# MicroRC-C.net
KiCad netlist of a schematic drawn in EAGLE
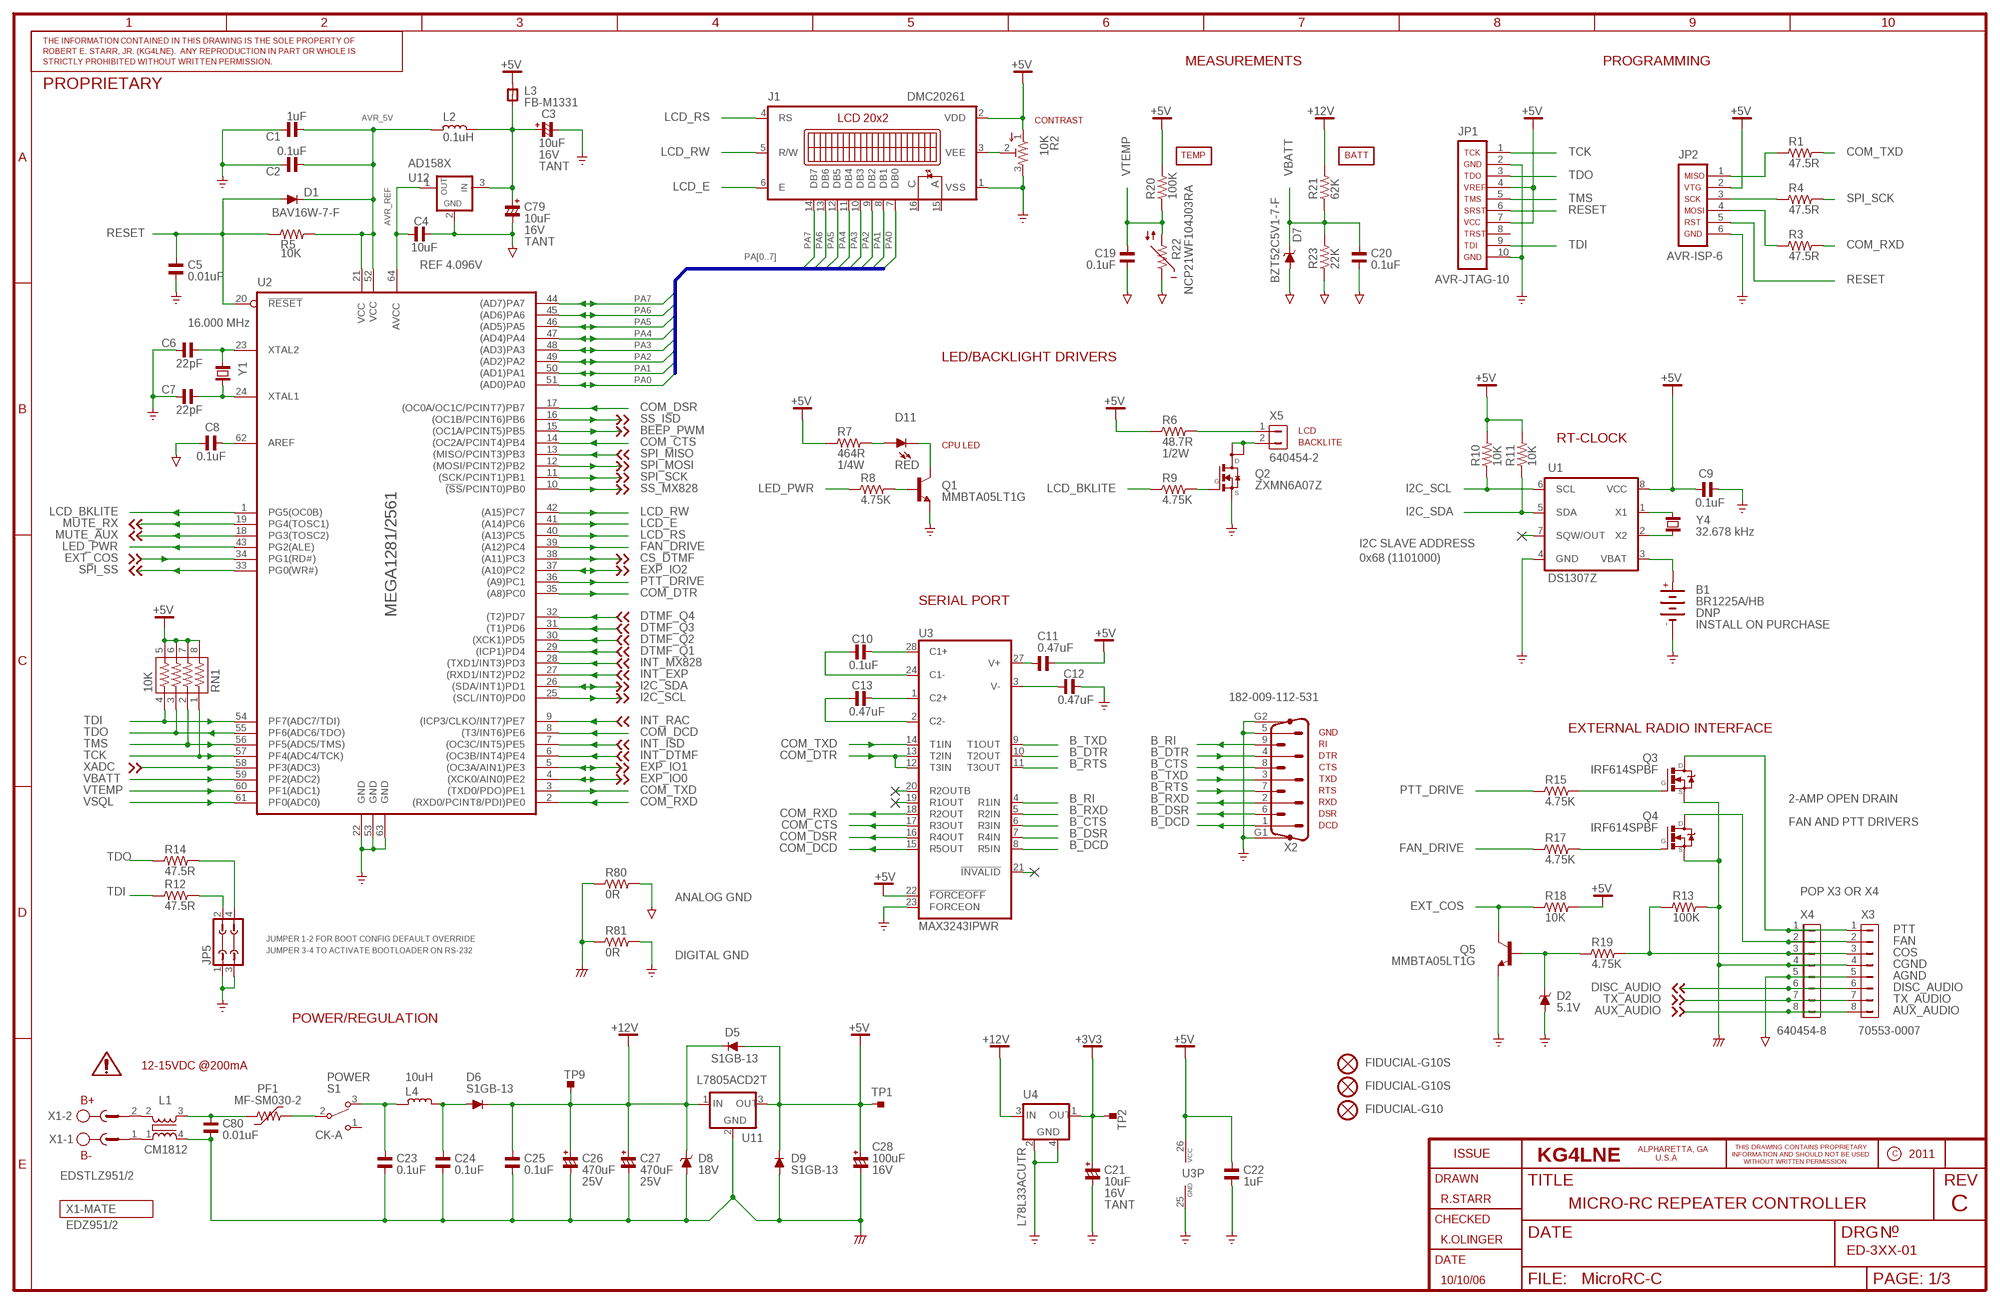
[diagram p0: schematic, sheet 1]
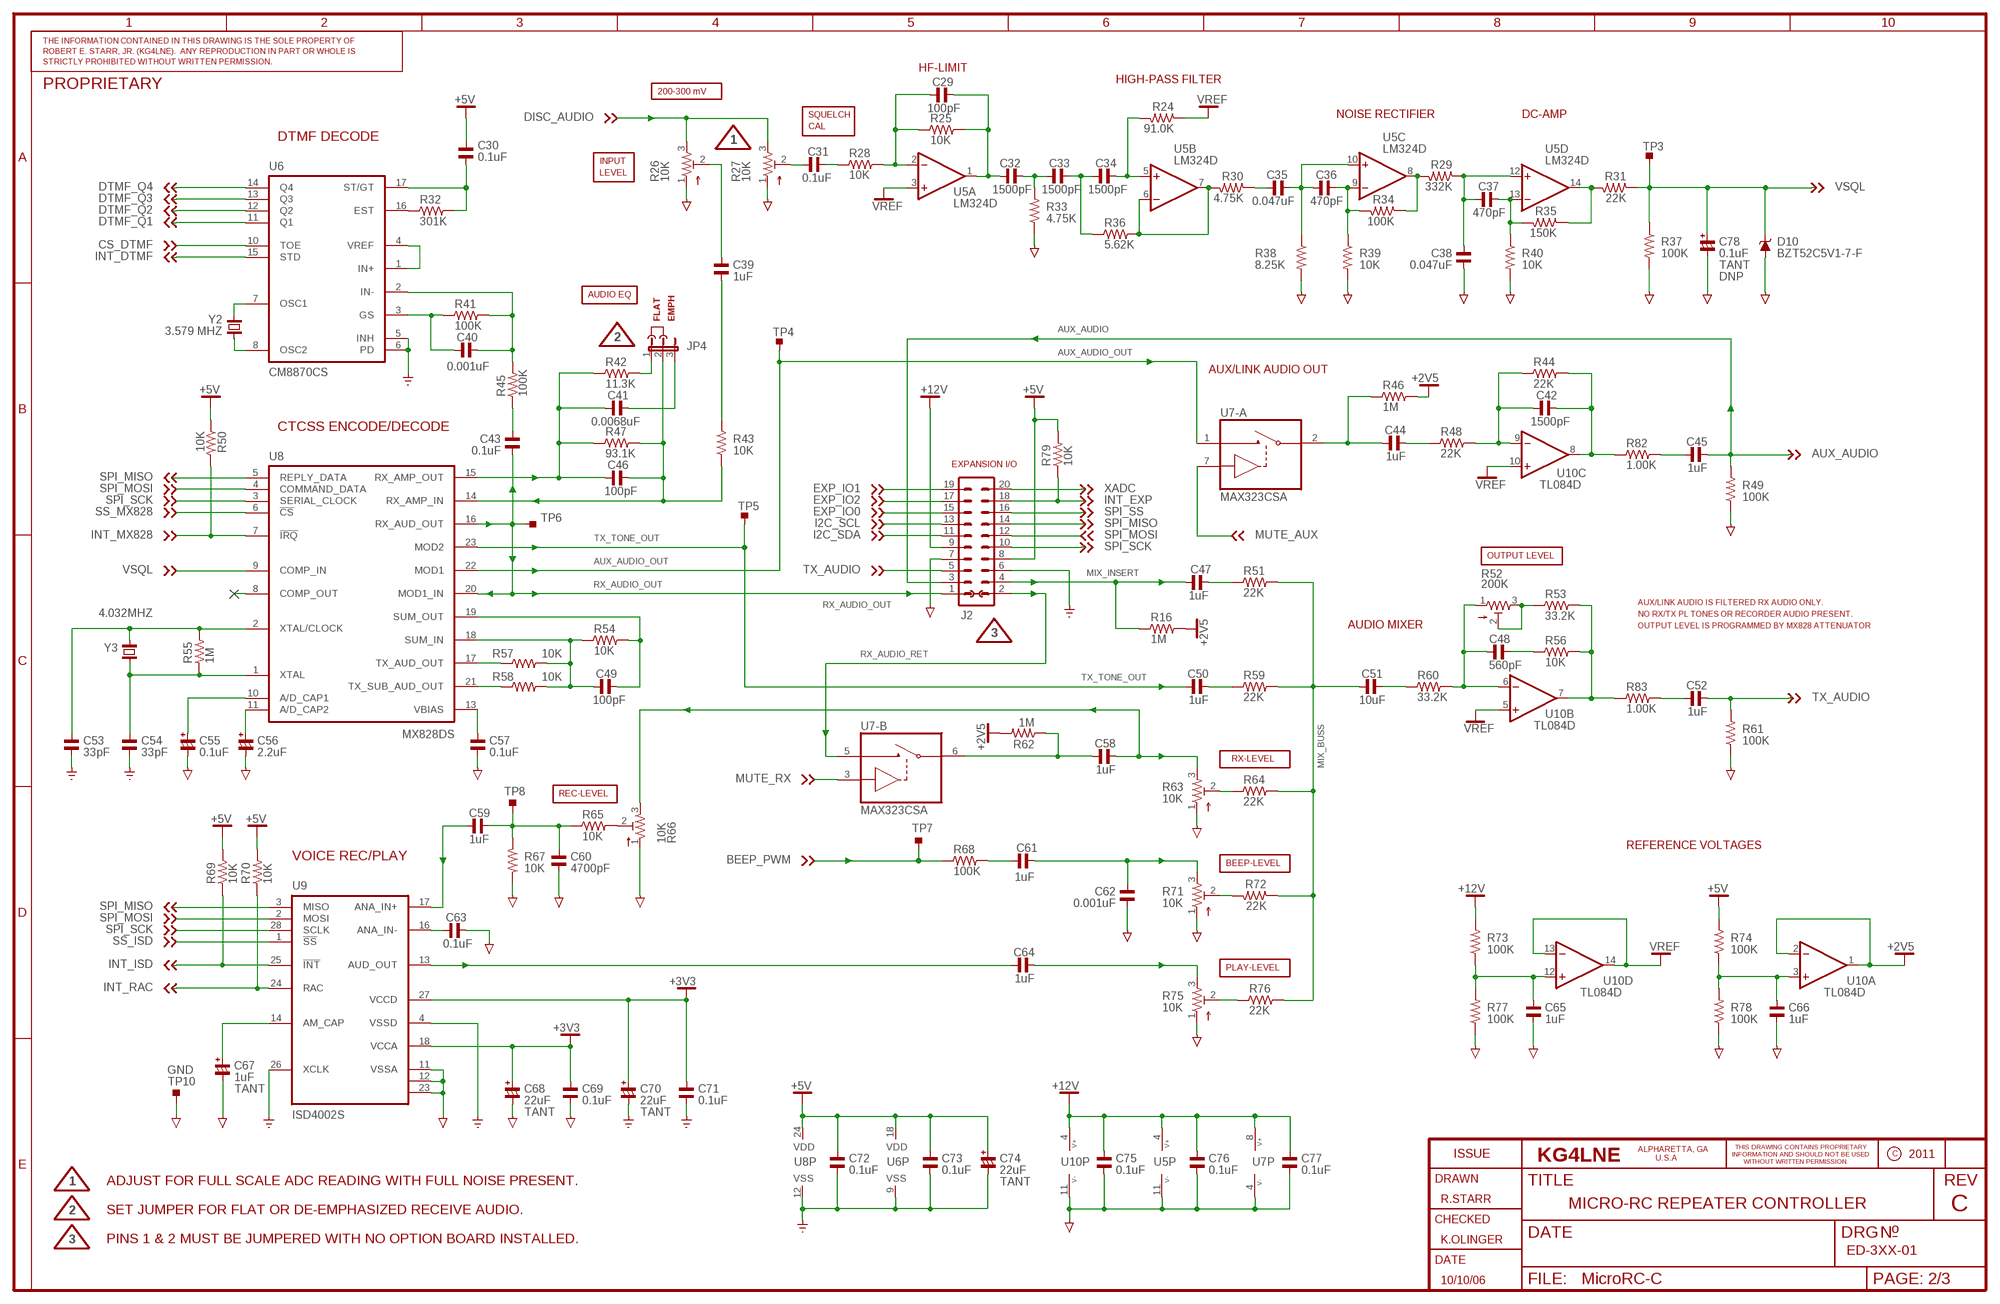
[diagram p1: schematic, sheet 2]
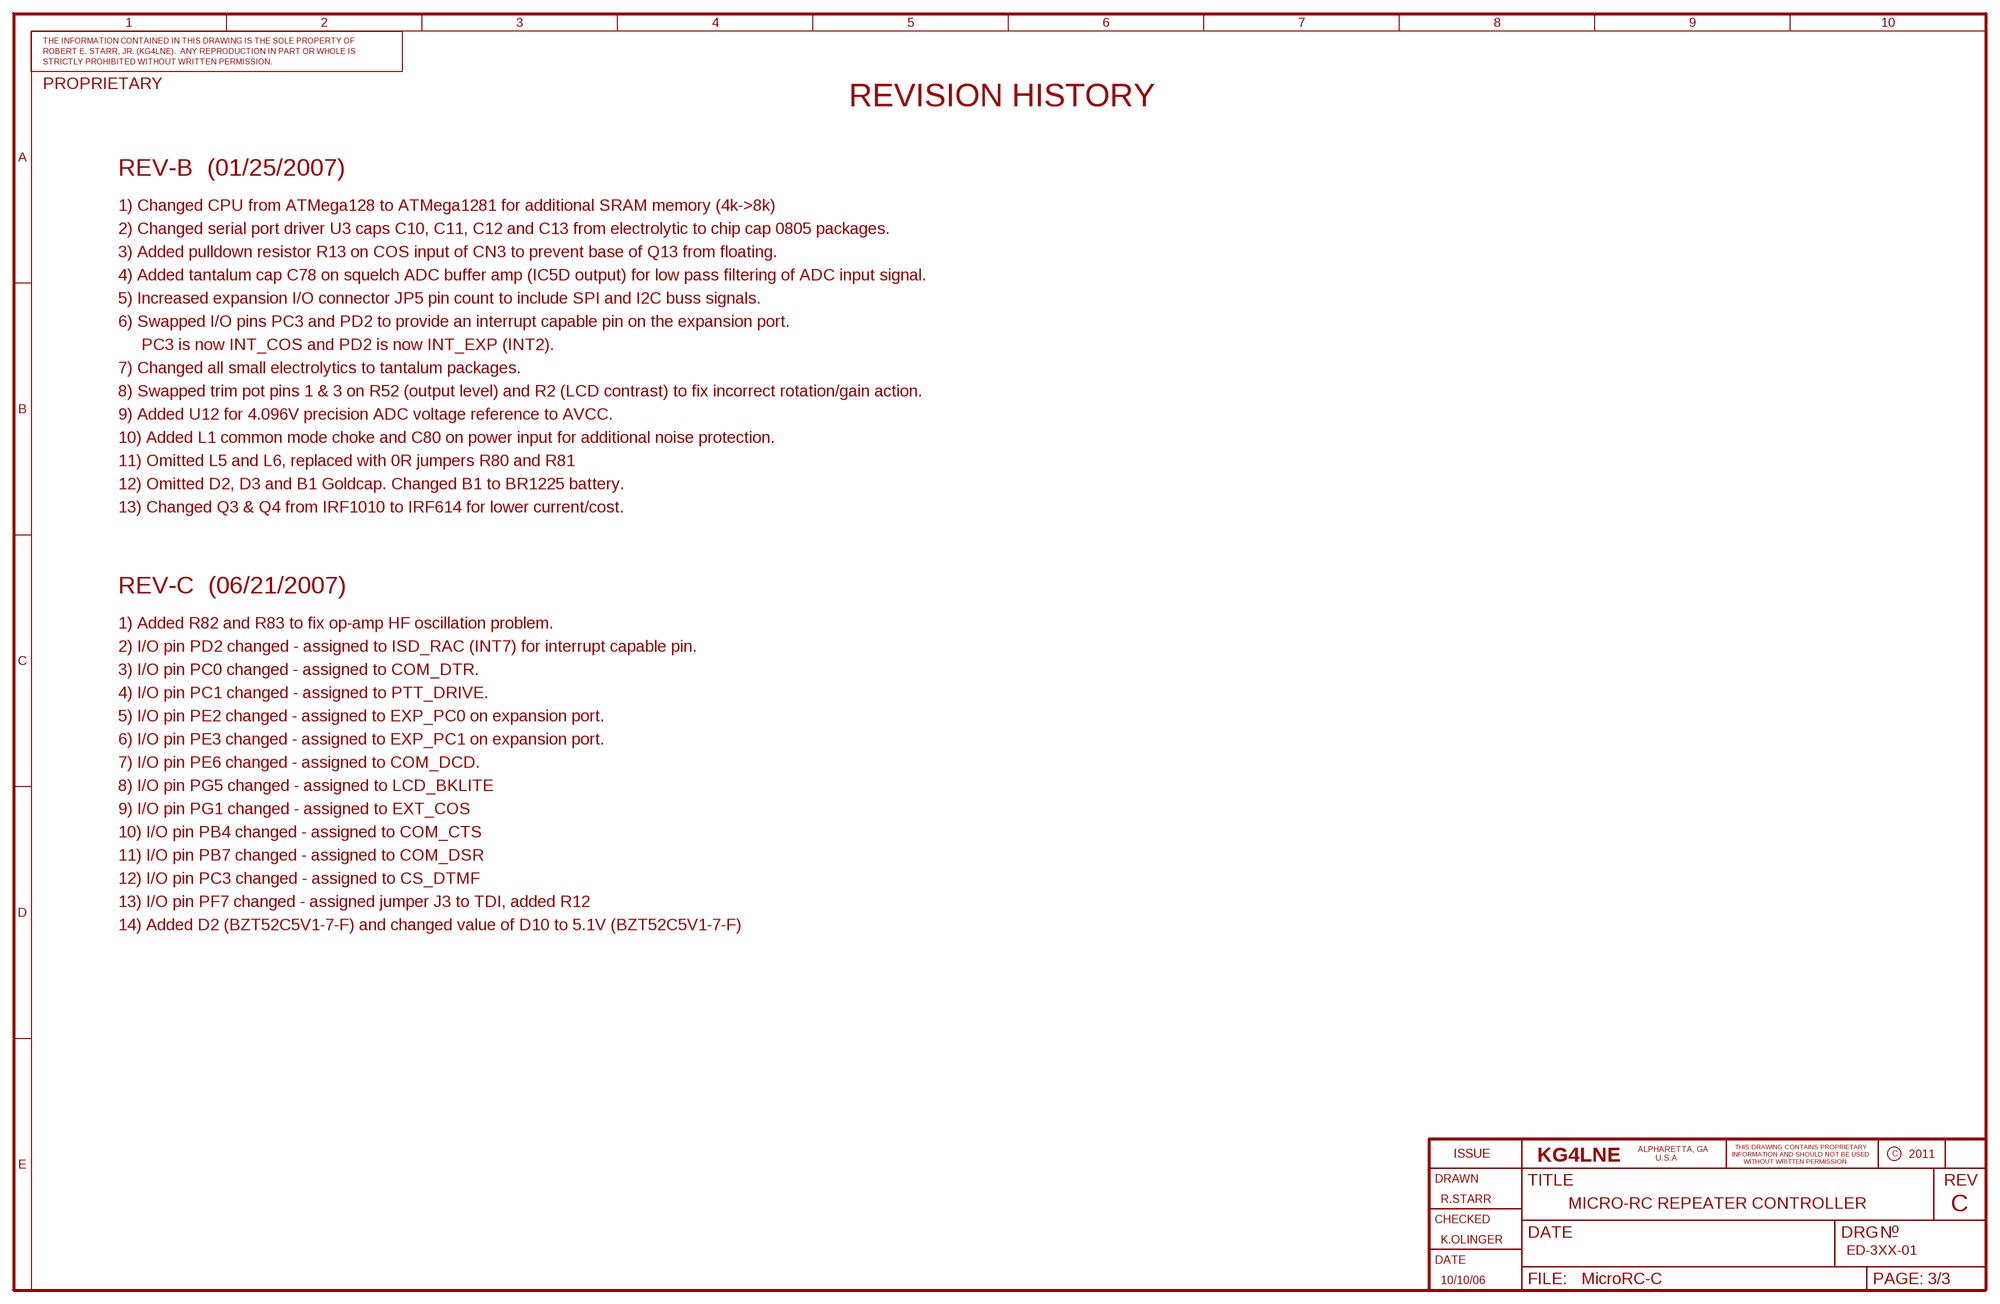
[diagram p2: schematic, sheet 3]

(export (version "E")
  (design (tool "Eeschema 10.0.6"))
  (components
    (comp (ref "B1")
      (value "BR1225A/HB")
      (footprint "eagle-import:BR1225")
      (fields (field (name "PLACE") "INSTALL ON PURCHASE"))
      (libsource (lib "eagle-import") (part "BR1225"))
    )
    (comp (ref "C1")
      (value "1uF")
      (footprint "eagle-import:C0805")
      (fields (field (name "PARTNO") "C0805C105Z3VACTU"))
      (libsource (lib "eagle-import") (part "C_0805"))
    )
    (comp (ref "C2")
      (value "0.1uF")
      (footprint "eagle-import:C0805")
      (fields (field (name "PARTNO") "C0805F104K5RACTU"))
      (libsource (lib "eagle-import") (part "C_0805"))
    )
    (comp (ref "C3")
      (value "10uF")
      (footprint "eagle-import:C3528_T")
      (fields
        (field (name "PARTNO") "T491B106M016AT")
        (field (name "TYPE") "TANT")
        (field (name "VOLT") "16V")
      )
      (libsource (lib "eagle-import") (part "CP_3528"))
    )
    (comp (ref "C4")
      (value "10uF")
      (footprint "eagle-import:C0805")
      (fields (field (name "PARTNO") "C0805C106K9PACTU"))
      (libsource (lib "eagle-import") (part "C_0805"))
    )
    (comp (ref "C5")
      (value "0.01uF")
      (footprint "eagle-import:C0805")
      (fields (field (name "PARTNO") "C0805C103K5RACTU"))
      (libsource (lib "eagle-import") (part "C_0805"))
    )
    (comp (ref "C6")
      (value "22pF")
      (footprint "eagle-import:C0805")
      (fields (field (name "PARTNO") "C0805C220J5GACTU"))
      (libsource (lib "eagle-import") (part "C_0805"))
    )
    (comp (ref "C7")
      (value "22pF")
      (footprint "eagle-import:C0805")
      (fields (field (name "PARTNO") "C0805C220J5GACTU"))
      (libsource (lib "eagle-import") (part "C_0805"))
    )
    (comp (ref "C8")
      (value "0.1uF")
      (footprint "eagle-import:C0805")
      (fields (field (name "PARTNO") "C0805F104K5RACTU"))
      (libsource (lib "eagle-import") (part "C_0805"))
    )
    (comp (ref "C9")
      (value "0.1uF")
      (footprint "eagle-import:C0805")
      (fields (field (name "PARTNO") "C0805F104K5RACTU"))
      (libsource (lib "eagle-import") (part "C_0805"))
    )
    (comp (ref "C10")
      (value "0.1uF")
      (footprint "eagle-import:C0805")
      (fields (field (name "PARTNO") "C0805F104K5RACTU"))
      (libsource (lib "eagle-import") (part "C_0805"))
    )
    (comp (ref "C11")
      (value "0.47uF")
      (footprint "eagle-import:C0805")
      (fields (field (name "PARTNO") "C0805F474K3RACTU"))
      (libsource (lib "eagle-import") (part "C_0805"))
    )
    (comp (ref "C12")
      (value "0.47uF")
      (footprint "eagle-import:C0805")
      (fields (field (name "PARTNO") "C0805F474K3RACTU"))
      (libsource (lib "eagle-import") (part "C_0805"))
    )
    (comp (ref "C13")
      (value "0.47uF")
      (footprint "eagle-import:C0805")
      (fields (field (name "PARTNO") "C0805F474K3RACTU"))
      (libsource (lib "eagle-import") (part "C_0805"))
    )
    (comp (ref "C19")
      (value "0.1uF")
      (footprint "eagle-import:C0805")
      (fields (field (name "PARTNO") "C0805F104K5RACTU"))
      (libsource (lib "eagle-import") (part "C_0805"))
    )
    (comp (ref "C20")
      (value "0.1uF")
      (footprint "eagle-import:C0805")
      (fields (field (name "PARTNO") "C0805F104K5RACTU"))
      (libsource (lib "eagle-import") (part "C_0805"))
    )
    (comp (ref "C21")
      (value "10uF")
      (footprint "eagle-import:C3528_T")
      (fields
        (field (name "PARTNO") "T491B106M016AT")
        (field (name "TYPE") "TANT")
        (field (name "VOLT") "16V")
      )
      (libsource (lib "eagle-import") (part "CP_3528"))
    )
    (comp (ref "C22")
      (value "1uF")
      (footprint "eagle-import:C0805")
      (fields (field (name "PARTNO") "C0805C105Z3VACTU"))
      (libsource (lib "eagle-import") (part "C_0805"))
    )
    (comp (ref "C23")
      (value "0.1uF")
      (footprint "eagle-import:C1206")
      (fields (field (name "PARTNO") "C1206C104K5RACTU"))
      (libsource (lib "eagle-import") (part "C_1206"))
    )
    (comp (ref "C24")
      (value "0.1uF")
      (footprint "eagle-import:C1206")
      (fields (field (name "PARTNO") "C1206C104K5RACTU"))
      (libsource (lib "eagle-import") (part "C_1206"))
    )
    (comp (ref "C25")
      (value "0.1uF")
      (footprint "eagle-import:C1206")
      (fields (field (name "PARTNO") "C1206C104K5RACTU"))
      (libsource (lib "eagle-import") (part "C_1206"))
    )
    (comp (ref "C26")
      (value "470uF")
      (footprint "eagle-import:CSV-G")
      (fields (field (name "PARTNO") "EEE-1EA471P") (field (name "VOLT") "25V"))
      (libsource (lib "eagle-import") (part "CP_SV-G"))
    )
    (comp (ref "C27")
      (value "470uF")
      (footprint "eagle-import:CSV-G")
      (fields (field (name "PARTNO") "EEE-1EA471P") (field (name "VOLT") "25V"))
      (libsource (lib "eagle-import") (part "CP_SV-G"))
    )
    (comp (ref "C28")
      (value "100uF")
      (footprint "eagle-import:CSV-E_F")
      (fields (field (name "PARTNO") "EEE-1CA101P") (field (name "VOLT") "16V"))
      (libsource (lib "eagle-import") (part "CP_SV-E/F"))
    )
    (comp (ref "C79")
      (value "10uF")
      (footprint "eagle-import:C3528_T")
      (fields
        (field (name "PARTNO") "T491B106M016AT")
        (field (name "TYPE") "TANT")
        (field (name "VOLT") "16V")
      )
      (libsource (lib "eagle-import") (part "CP_3528"))
    )
    (comp (ref "C80")
      (value "0.01uF")
      (footprint "eagle-import:C1206")
      (fields (field (name "PARTNO") "12065C103KAT2A"))
      (libsource (lib "eagle-import") (part "C_1206"))
    )
    (comp (ref "D1")
      (value "BAV16W-7-F")
      (footprint "eagle-import:SOD123")
      (libsource (lib "eagle-import") (part "DIODE-SOD123"))
    )
    (comp (ref "D2")
      (value "5.1V")
      (footprint "eagle-import:SOD123")
      (fields (field (name "PARTNO") "BZT52C5V1-7-F"))
      (libsource (lib "eagle-import") (part "ZENER-DIODESOD123"))
    )
    (comp (ref "D5")
      (value "S1GB-13")
      (footprint "eagle-import:SMB")
      (fields (field (name "PARTNO") "RS1GB-13-F"))
      (libsource (lib "eagle-import") (part "S1GB-13"))
    )
    (comp (ref "D6")
      (value "S1GB-13")
      (footprint "eagle-import:SMB")
      (fields (field (name "PARTNO") "RS1GB-13-F"))
      (libsource (lib "eagle-import") (part "S1GB-13"))
    )
    (comp (ref "D7")
      (value "BZT52C5V1-7-F")
      (footprint "eagle-import:SOD123")
      (fields (field (name "PARTNO") "BZT52C5V6-7-F"))
      (libsource (lib "eagle-import") (part "ZENER-DIODESOD123"))
    )
    (comp (ref "D8")
      (value "18V")
      (footprint "eagle-import:SMB")
      (fields (field (name "PARTNO") "1SMB5931BT3G"))
      (libsource (lib "eagle-import") (part "ZENER-DIODESMB"))
    )
    (comp (ref "D9")
      (value "S1GB-13")
      (footprint "eagle-import:SMB")
      (fields (field (name "PARTNO") "RS1GB-13-F"))
      (libsource (lib "eagle-import") (part "S1GB-13"))
    )
    (comp (ref "D11")
      (value "RED")
      (footprint "eagle-import:LED535")
      (fields (field (name "PARTNO") "5350T5"))
      (libsource (lib "eagle-import") (part "LED535XX"))
    )
    (comp (ref "FIDUCIAL1")
      (value "FIDUCIAL-G10S")
      (footprint "eagle-import:G10S")
      (libsource (lib "eagle-import") (part "FIDUCIAL-G10S"))
    )
    (comp (ref "FIDUCIAL2")
      (value "FIDUCIAL-G10S")
      (footprint "eagle-import:G10S")
      (libsource (lib "eagle-import") (part "FIDUCIAL-G10S"))
    )
    (comp (ref "FIDUCIAL3")
      (value "FIDUCIAL-G10")
      (footprint "eagle-import:G10")
      (libsource (lib "eagle-import") (part "FIDUCIAL-G10"))
    )
    (comp (ref "J1")
      (value "DMC20261")
      (footprint "eagle-import:DMC20261")
      (libsource (lib "eagle-import") (part "DMC20261"))
    )
    (comp (ref "JP1")
      (value "AVR-JTAG-10")
      (footprint "eagle-import:AVR-JTAG-10")
      (libsource (lib "eagle-import") (part "AVR-JTAG-10"))
    )
    (comp (ref "JP2")
      (value "AVR-ISP-6")
      (footprint "eagle-import:AVR-ISP-6")
      (libsource (lib "eagle-import") (part "AVR-ISP-6"))
    )
    (comp (ref "JP5")
      (value "JP2Q")
      (footprint "eagle-import:JP2Q")
      (libsource (lib "eagle-import") (part "JP2Q"))
    )
    (comp (ref "L1")
      (value "CM1812")
      (footprint "eagle-import:CM1812")
      (fields (field (name "PARTNO") "CM1812R600R-10"))
      (libsource (lib "eagle-import") (part "CM1812"))
    )
    (comp (ref "L2")
      (value "0.1uH")
      (footprint "eagle-import:L1206")
      (fields (field (name "PARTNO") "PM1210-R10J"))
      (libsource (lib "eagle-import") (part "L_1206"))
    )
    (comp (ref "L3")
      (value "FB-M1331")
      (footprint "eagle-import:L1206")
      (fields (field (name "PARTNO") "PM2001-200"))
      (libsource (lib "eagle-import") (part "FB_1206"))
    )
    (comp (ref "L4")
      (value "10uH")
      (footprint "eagle-import:PM-13")
      (fields (field (name "PARTNO") "PM3308-100M"))
      (libsource (lib "eagle-import") (part "L-PM3308"))
    )
    (comp (ref "PF1")
      (value "MF-SM030-2")
      (footprint "eagle-import:SMD-7555")
      (libsource (lib "eagle-import") (part "POLYSWITCH-SMD-7555"))
    )
    (comp (ref "Q1")
      (value "MMBTA05LT1G")
      (footprint "eagle-import:SOT23")
      (libsource (lib "eagle-import") (part "MMBTA05"))
    )
    (comp (ref "Q2")
      (value "ZXMN6A07Z")
      (footprint "eagle-import:SOT89")
      (fields (field (name "PARTNO") "ZXMN6A07ZTA"))
      (libsource (lib "eagle-import") (part "ZXMN6A07Z"))
    )
    (comp (ref "Q3")
      (value "IRF614SPBF")
      (footprint "eagle-import:D2PAK")
      (libsource (lib "eagle-import") (part "IRF614"))
    )
    (comp (ref "Q4")
      (value "IRF614SPBF")
      (footprint "eagle-import:D2PAK")
      (libsource (lib "eagle-import") (part "IRF614"))
    )
    (comp (ref "Q5")
      (value "MMBTA05LT1G")
      (footprint "eagle-import:SOT23")
      (libsource (lib "eagle-import") (part "MMBTA05"))
    )
    (comp (ref "R1")
      (value "47.5R")
      (footprint "eagle-import:R0805")
      (fields (field (name "PARTNO") "ERJ-6ENF47R5V"))
      (libsource (lib "eagle-import") (part "R_0805"))
    )
    (comp (ref "R2")
      (value "10K")
      (footprint "eagle-import:EVM-L4G")
      (fields (field (name "PARTNO") "EVM-L4GA00B14"))
      (libsource (lib "eagle-import") (part "TRIM_EU-EVM-L4G"))
    )
    (comp (ref "R3")
      (value "47.5R")
      (footprint "eagle-import:R0805")
      (fields (field (name "PARTNO") "ERJ-6ENF47R5V"))
      (libsource (lib "eagle-import") (part "R_0805"))
    )
    (comp (ref "R4")
      (value "47.5R")
      (footprint "eagle-import:R0805")
      (fields (field (name "PARTNO") "ERJ-6ENF47R5V"))
      (libsource (lib "eagle-import") (part "R_0805"))
    )
    (comp (ref "R5")
      (value "10K")
      (footprint "eagle-import:R0805")
      (fields (field (name "PARTNO") "ERJ-6ENF1002V"))
      (libsource (lib "eagle-import") (part "R_0805"))
    )
    (comp (ref "R6")
      (value "48.7R")
      (footprint "eagle-import:R2010")
      (fields (field (name "PARTNO") "ERJ-12SF48R7U") (field (name "RATE") "1/2W"))
      (libsource (lib "eagle-import") (part "R_2010"))
    )
    (comp (ref "R7")
      (value "464R")
      (footprint "eagle-import:R1210")
      (fields (field (name "PARTNO") "ERJ-14NF4640U") (field (name "RATE") "1/4W"))
      (libsource (lib "eagle-import") (part "R_1210"))
    )
    (comp (ref "R8")
      (value "4.75K")
      (footprint "eagle-import:R0805")
      (fields (field (name "PARTNO") "ERJ-6ENF4751V"))
      (libsource (lib "eagle-import") (part "R_0805"))
    )
    (comp (ref "R9")
      (value "4.75K")
      (footprint "eagle-import:R0805")
      (fields (field (name "PARTNO") "ERJ-6ENF4751V"))
      (libsource (lib "eagle-import") (part "R_0805"))
    )
    (comp (ref "R10")
      (value "10K")
      (footprint "eagle-import:R0805")
      (fields (field (name "PARTNO") "ERJ-6ENF1002V"))
      (libsource (lib "eagle-import") (part "R_0805"))
    )
    (comp (ref "R11")
      (value "10K")
      (footprint "eagle-import:R0805")
      (fields (field (name "PARTNO") "ERJ-6ENF1002V"))
      (libsource (lib "eagle-import") (part "R_0805"))
    )
    (comp (ref "R12")
      (value "47.5R")
      (footprint "eagle-import:R0805")
      (fields (field (name "PARTNO") "ERJ-6ENF47R5V"))
      (libsource (lib "eagle-import") (part "R_0805"))
    )
    (comp (ref "R13")
      (value "100K")
      (footprint "eagle-import:R0805")
      (fields (field (name "PARTNO") "ERJ-6ENF1003V"))
      (libsource (lib "eagle-import") (part "R_0805"))
    )
    (comp (ref "R14")
      (value "47.5R")
      (footprint "eagle-import:R0805")
      (fields (field (name "PARTNO") "ERJ-6ENF47R5V"))
      (libsource (lib "eagle-import") (part "R_0805"))
    )
    (comp (ref "R15")
      (value "4.75K")
      (footprint "eagle-import:R0805")
      (fields (field (name "PARTNO") "ERJ-6ENF4751V"))
      (libsource (lib "eagle-import") (part "R_0805"))
    )
    (comp (ref "R17")
      (value "4.75K")
      (footprint "eagle-import:R0805")
      (fields (field (name "PARTNO") "ERJ-6ENF4751V"))
      (libsource (lib "eagle-import") (part "R_0805"))
    )
    (comp (ref "R18")
      (value "10K")
      (footprint "eagle-import:R0805")
      (fields (field (name "PARTNO") "ERJ-6ENF1002V"))
      (libsource (lib "eagle-import") (part "R_0805"))
    )
    (comp (ref "R19")
      (value "4.75K")
      (footprint "eagle-import:R0805")
      (fields (field (name "PARTNO") "ERJ-6ENF4751V"))
      (libsource (lib "eagle-import") (part "R_0805"))
    )
    (comp (ref "R20")
      (value "100K")
      (footprint "eagle-import:R0805")
      (fields (field (name "PARTNO") "ERJ-6ENF1003V"))
      (libsource (lib "eagle-import") (part "R_0805"))
    )
    (comp (ref "R21")
      (value "62K")
      (footprint "eagle-import:R0805")
      (fields (field (name "PARTNO") "ERJ-6ENF6192V"))
      (libsource (lib "eagle-import") (part "R_0805"))
    )
    (comp (ref "R22")
      (value "NCP21WF104J03RA")
      (footprint "eagle-import:R0805")
      (libsource (lib "eagle-import") (part "NCP-0805"))
    )
    (comp (ref "R23")
      (value "22K")
      (footprint "eagle-import:R0805")
      (fields (field (name "PARTNO") "ERJ-6ENF2212V"))
      (libsource (lib "eagle-import") (part "R_0805"))
    )
    (comp (ref "R80")
      (value "0R")
      (footprint "eagle-import:R0805")
      (fields (field (name "PARTNO") "RC0805JR-070RL"))
      (libsource (lib "eagle-import") (part "R_0805"))
    )
    (comp (ref "R81")
      (value "0R")
      (footprint "eagle-import:R0805")
      (fields (field (name "PARTNO") "RC0805JR-070RL"))
      (libsource (lib "eagle-import") (part "R_0805"))
    )
    (comp (ref "RN1")
      (value "10K")
      (footprint "eagle-import:744-8")
      (fields (field (name "PARTNO") "744C083103JPTR"))
      (libsource (lib "eagle-import") (part "744-8"))
    )
    (comp (ref "S1")
      (value "CK-A")
      (footprint "eagle-import:CK-A")
      (fields (field (name "PARTNO") "2M1-SP1-T2-B4-M6RE"))
      (libsource (lib "eagle-import") (part "CK-A"))
    )
    (comp (ref "TP1")
      (value "TPTP10SQ")
      (footprint "eagle-import:TP10SQ")
      (libsource (lib "eagle-import") (part "TPTP10SQ"))
    )
    (comp (ref "TP2")
      (value "TPTP10SQ")
      (footprint "eagle-import:TP10SQ")
      (libsource (lib "eagle-import") (part "TPTP10SQ"))
    )
    (comp (ref "TP9")
      (value "TPTP10SQ")
      (footprint "eagle-import:TP10SQ")
      (libsource (lib "eagle-import") (part "TPTP10SQ"))
    )
    (comp (ref "U1")
      (value "DS1307Z")
      (footprint "eagle-import:SO08")
      (fields (field (name "PARTNO") "DS1307Z+"))
      (libsource (lib "eagle-import") (part "DS1307Z"))
    )
    (comp (ref "U2")
      (value "MEGA1281/2561")
      (footprint "eagle-import:TQFP64-AEB")
      (fields (field (name "PARTNO") "ATMEGA1281-16AU"))
      (libsource (lib "eagle-import") (part "MEGA1281/2561"))
    )
    (comp (ref "U3")
      (value "MAX3243IPWR")
      (footprint "eagle-import:TSSOP28")
      (fields (field (name "PARTNO") "MAX3243ECPWR"))
      (libsource (lib "eagle-import") (part "MAX3243PW"))
    )
    (comp (ref "U4")
      (value "L78L33ACUTR")
      (footprint "eagle-import:SOT89-4")
      (libsource (lib "eagle-import") (part "L78LXXCU/BU"))
    )
    (comp (ref "U11")
      (value "L7805ACD2T")
      (footprint "eagle-import:D2PAK")
      (libsource (lib "eagle-import") (part "L78XXD2T"))
    )
    (comp (ref "U12")
      (value "AD158X")
      (footprint "eagle-import:SOT23")
      (fields (field (name "PARTNO") "AD1584BRTZ-REEL7"))
      (libsource (lib "eagle-import") (part "AD158X"))
    )
    (comp (ref "X1")
      (value "EDSTLZ951/2")
      (footprint "eagle-import:951-2")
      (fields (field (name "PARTNO") "EDSTLZ951/2"))
      (libsource (lib "eagle-import") (part "EDSTLZ-2-951"))
    )
    (comp (ref "X2")
      (value "182-009-112-531")
      (footprint "eagle-import:NC182M9")
      (fields (field (name "PARTNO") "182-009-113R531"))
      (libsource (lib "eagle-import") (part "NC182M9-VS"))
    )
    (comp (ref "X3")
      (value "70553-0007")
      (footprint "eagle-import:70553-08")
      (fields (field (name "PLACE") "POP X3 OR X4"))
      (libsource (lib "eagle-import") (part "HDR-1X8-70553-?"))
    )
    (comp (ref "X4")
      (value "640454-8")
      (footprint "eagle-import:MTA08-100")
      (libsource (lib "eagle-import") (part "MTA08-100"))
    )
    (comp (ref "X5")
      (value "640454-2")
      (footprint "eagle-import:MTA-100-2V")
      (libsource (lib "eagle-import") (part "HDR-1X2-MTA-100"))
    )
    (comp (ref "Y1")
      (value "16.000 MHz")
      (footprint "eagle-import:TC38H")
      (fields (field (name "PARTNO") "ECS-160-18-9X"))
      (libsource (lib "eagle-import") (part "CRYTALTC38H"))
    )
    (comp (ref "Y4")
      (value "32.678 kHz")
      (footprint "eagle-import:TC26H")
      (fields (field (name "PARTNO") "ECS-.327-12.5-13X"))
      (libsource (lib "eagle-import") (part "CRYTALTC26H"))
    )
    (comp (ref "C29")
      (value "100pF")
      (footprint "eagle-import:C0805")
      (fields (field (name "PARTNO") "C0805C101J5GACTU"))
      (libsource (lib "eagle-import") (part "C_0805"))
    )
    (comp (ref "C30")
      (value "0.1uF")
      (footprint "eagle-import:C0805")
      (fields (field (name "PARTNO") "C0805F104K5RACTU"))
      (libsource (lib "eagle-import") (part "C_0805"))
    )
    (comp (ref "C31")
      (value "0.1uF")
      (footprint "eagle-import:C0805")
      (fields (field (name "PARTNO") "C0805F104K5RACTU"))
      (libsource (lib "eagle-import") (part "C_0805"))
    )
    (comp (ref "C32")
      (value "1500pF")
      (footprint "eagle-import:C0805")
      (fields (field (name "PARTNO") "C0805C152K5RACTU"))
      (libsource (lib "eagle-import") (part "C_0805"))
    )
    (comp (ref "C33")
      (value "1500pF")
      (footprint "eagle-import:C0805")
      (fields (field (name "PARTNO") "C0805C152K5RACTU"))
      (libsource (lib "eagle-import") (part "C_0805"))
    )
    (comp (ref "C34")
      (value "1500pF")
      (footprint "eagle-import:C0805")
      (fields (field (name "PARTNO") "C0805C152K5RACTU"))
      (libsource (lib "eagle-import") (part "C_0805"))
    )
    (comp (ref "C35")
      (value "0.047uF")
      (footprint "eagle-import:C0805")
      (fields (field (name "PARTNO") "C0805C473K5RACTU"))
      (libsource (lib "eagle-import") (part "C_0805"))
    )
    (comp (ref "C36")
      (value "470pF")
      (footprint "eagle-import:C0805")
      (fields (field (name "PARTNO") "C0805C471J5GACTU"))
      (libsource (lib "eagle-import") (part "C_0805"))
    )
    (comp (ref "C37")
      (value "470pF")
      (footprint "eagle-import:C0805")
      (fields (field (name "PARTNO") "C0805C471J5GACTU"))
      (libsource (lib "eagle-import") (part "C_0805"))
    )
    (comp (ref "C38")
      (value "0.047uF")
      (footprint "eagle-import:C0805")
      (fields (field (name "PARTNO") "C0805C473K5RACTU"))
      (libsource (lib "eagle-import") (part "C_0805"))
    )
    (comp (ref "C39")
      (value "1uF")
      (footprint "eagle-import:C0805")
      (fields (field (name "PARTNO") "C0805C105Z3VACTU"))
      (libsource (lib "eagle-import") (part "C_0805"))
    )
    (comp (ref "C40")
      (value "0.001uF")
      (footprint "eagle-import:C0805")
      (fields (field (name "PARTNO") "C0805C102K5RACTU"))
      (libsource (lib "eagle-import") (part "C_0805"))
    )
    (comp (ref "C41")
      (value "0.0068uF")
      (footprint "eagle-import:C0805")
      (fields (field (name "PARTNO") "C0805C682K5RACTU"))
      (libsource (lib "eagle-import") (part "C_0805"))
    )
    (comp (ref "C42")
      (value "1500pF")
      (footprint "eagle-import:C0805")
      (fields (field (name "PARTNO") "C0805C152K5RACTU"))
      (libsource (lib "eagle-import") (part "C_0805"))
    )
    (comp (ref "C43")
      (value "0.1uF")
      (footprint "eagle-import:C0805")
      (fields (field (name "PARTNO") "C0805F104K5RACTU"))
      (libsource (lib "eagle-import") (part "C_0805"))
    )
    (comp (ref "C44")
      (value "1uF")
      (footprint "eagle-import:C0805")
      (fields (field (name "PARTNO") "C0805C105Z3VACTU"))
      (libsource (lib "eagle-import") (part "C_0805"))
    )
    (comp (ref "C45")
      (value "1uF")
      (footprint "eagle-import:C0805")
      (fields (field (name "PARTNO") "C0805C105Z3VACTU"))
      (libsource (lib "eagle-import") (part "C_0805"))
    )
    (comp (ref "C46")
      (value "100pF")
      (footprint "eagle-import:C0805")
      (fields (field (name "PARTNO") "C0805C101J5GACTU"))
      (libsource (lib "eagle-import") (part "C_0805"))
    )
    (comp (ref "C47")
      (value "1uF")
      (footprint "eagle-import:C0805")
      (fields (field (name "PARTNO") "C0805C105Z3VACTU"))
      (libsource (lib "eagle-import") (part "C_0805"))
    )
    (comp (ref "C48")
      (value "560pF")
      (footprint "eagle-import:C0805")
      (fields (field (name "PARTNO") "C0805C561J5GACTU"))
      (libsource (lib "eagle-import") (part "C_0805"))
    )
    (comp (ref "C49")
      (value "100pF")
      (footprint "eagle-import:C0805")
      (fields (field (name "PARTNO") "C0805C101J5GACTU"))
      (libsource (lib "eagle-import") (part "C_0805"))
    )
    (comp (ref "C50")
      (value "1uF")
      (footprint "eagle-import:C0805")
      (fields (field (name "PARTNO") "C0805C105Z3VACTU"))
      (libsource (lib "eagle-import") (part "C_0805"))
    )
    (comp (ref "C51")
      (value "10uF")
      (footprint "eagle-import:C0805")
      (fields (field (name "PARTNO") "C0805C106K9PACTU"))
      (libsource (lib "eagle-import") (part "C_0805"))
    )
    (comp (ref "C52")
      (value "1uF")
      (footprint "eagle-import:C0805")
      (fields (field (name "PARTNO") "C0805C105Z3VACTU"))
      (libsource (lib "eagle-import") (part "C_0805"))
    )
    (comp (ref "C53")
      (value "33pF")
      (footprint "eagle-import:C0805")
      (fields (field (name "PARTNO") "C0805C330J5GACTU"))
      (libsource (lib "eagle-import") (part "C_0805"))
    )
    (comp (ref "C54")
      (value "33pF")
      (footprint "eagle-import:C0805")
      (fields (field (name "PARTNO") "C0805C330J5GACTU"))
      (libsource (lib "eagle-import") (part "C_0805"))
    )
    (comp (ref "C55")
      (value "0.1uF")
      (footprint "eagle-import:C3216_T")
      (fields (field (name "PARTNO") "T491A104K035AT"))
      (libsource (lib "eagle-import") (part "CP_3216"))
    )
    (comp (ref "C56")
      (value "2.2uF")
      (footprint "eagle-import:C3216_T")
      (fields (field (name "PARTNO") "T491A225K010AT"))
      (libsource (lib "eagle-import") (part "CP_3216"))
    )
    (comp (ref "C57")
      (value "0.1uF")
      (footprint "eagle-import:C0805")
      (fields (field (name "PARTNO") "C0805F104K5RACTU"))
      (libsource (lib "eagle-import") (part "C_0805"))
    )
    (comp (ref "C58")
      (value "1uF")
      (footprint "eagle-import:C0805")
      (fields (field (name "PARTNO") "C0805C105Z3VACTU"))
      (libsource (lib "eagle-import") (part "C_0805"))
    )
    (comp (ref "C59")
      (value "1uF")
      (footprint "eagle-import:C0805")
      (fields (field (name "PARTNO") "C0805C105Z3VACTU"))
      (libsource (lib "eagle-import") (part "C_0805"))
    )
    (comp (ref "C60")
      (value "4700pF")
      (footprint "eagle-import:C0805")
      (fields (field (name "PARTNO") "C0805C472K5RACTU"))
      (libsource (lib "eagle-import") (part "C_0805"))
    )
    (comp (ref "C61")
      (value "1uF")
      (footprint "eagle-import:C0805")
      (fields (field (name "PARTNO") "C0805C105Z3VACTU"))
      (libsource (lib "eagle-import") (part "C_0805"))
    )
    (comp (ref "C62")
      (value "0.001uF")
      (footprint "eagle-import:C0805")
      (fields (field (name "PARTNO") "C0805C102K5RACTU"))
      (libsource (lib "eagle-import") (part "C_0805"))
    )
    (comp (ref "C63")
      (value "0.1uF")
      (footprint "eagle-import:C0805")
      (fields (field (name "PARTNO") "C0805F104K5RACTU"))
      (libsource (lib "eagle-import") (part "C_0805"))
    )
    (comp (ref "C64")
      (value "1uF")
      (footprint "eagle-import:C0805")
      (fields (field (name "PARTNO") "C0805C105Z3VACTU"))
      (libsource (lib "eagle-import") (part "C_0805"))
    )
    (comp (ref "C65")
      (value "1uF")
      (footprint "eagle-import:C0805")
      (fields (field (name "PARTNO") "C0805C105Z3VACTU"))
      (libsource (lib "eagle-import") (part "C_0805"))
    )
    (comp (ref "C66")
      (value "1uF")
      (footprint "eagle-import:C0805")
      (fields (field (name "PARTNO") "C0805C105Z3VACTU"))
      (libsource (lib "eagle-import") (part "C_0805"))
    )
    (comp (ref "C67")
      (value "1uF")
      (footprint "eagle-import:C3216_T")
      (fields (field (name "PARTNO") "T491A105K016AT") (field (name "TYPE") "TANT"))
      (libsource (lib "eagle-import") (part "CP_3216"))
    )
    (comp (ref "C68")
      (value "22uF")
      (footprint "eagle-import:C3528_T")
      (fields (field (name "PARTNO") "T491B226M016AT") (field (name "TYPE") "TANT"))
      (libsource (lib "eagle-import") (part "CP_3528"))
    )
    (comp (ref "C69")
      (value "0.1uF")
      (footprint "eagle-import:C0805")
      (fields (field (name "PARTNO") "C0805F104K5RACTU"))
      (libsource (lib "eagle-import") (part "C_0805"))
    )
    (comp (ref "C70")
      (value "22uF")
      (footprint "eagle-import:C3528_T")
      (fields (field (name "PARTNO") "T491B226M016AT") (field (name "TYPE") "TANT"))
      (libsource (lib "eagle-import") (part "CP_3528"))
    )
    (comp (ref "C71")
      (value "0.1uF")
      (footprint "eagle-import:C0805")
      (fields (field (name "PARTNO") "C0805F104K5RACTU"))
      (libsource (lib "eagle-import") (part "C_0805"))
    )
    (comp (ref "C72")
      (value "0.1uF")
      (footprint "eagle-import:C0805")
      (fields (field (name "PARTNO") "C0805F104K5RACTU"))
      (libsource (lib "eagle-import") (part "C_0805"))
    )
    (comp (ref "C73")
      (value "0.1uF")
      (footprint "eagle-import:C0805")
      (fields (field (name "PARTNO") "C0805F104K5RACTU"))
      (libsource (lib "eagle-import") (part "C_0805"))
    )
    (comp (ref "C74")
      (value "22uF")
      (footprint "eagle-import:C3528_T")
      (fields (field (name "PARTNO") "T491B226M016AT") (field (name "TYPE") "TANT"))
      (libsource (lib "eagle-import") (part "CP_3528"))
    )
    (comp (ref "C75")
      (value "0.1uF")
      (footprint "eagle-import:C0805")
      (fields (field (name "PARTNO") "C0805F104K5RACTU"))
      (libsource (lib "eagle-import") (part "C_0805"))
    )
    (comp (ref "C76")
      (value "0.1uF")
      (footprint "eagle-import:C0805")
      (fields (field (name "PARTNO") "C0805F104K5RACTU"))
      (libsource (lib "eagle-import") (part "C_0805"))
    )
    (comp (ref "C77")
      (value "0.1uF")
      (footprint "eagle-import:C0805")
      (fields (field (name "PARTNO") "C0805F104K5RACTU"))
      (libsource (lib "eagle-import") (part "C_0805"))
    )
    (comp (ref "C78")
      (value "0.1uF")
      (footprint "eagle-import:C3216_T")
      (fields (field (name "PARTNO") "DNP") (field (name "TYPE") "TANT"))
      (libsource (lib "eagle-import") (part "CP_3216"))
    )
    (comp (ref "D10")
      (value "BZT52C5V1-7-F")
      (footprint "eagle-import:SOD123")
      (fields (field (name "PARTNO") "BZT52C5V6-7-F"))
      (libsource (lib "eagle-import") (part "ZENER-DIODESOD123"))
    )
    (comp (ref "J2")
      (value "MA10-2")
      (footprint "eagle-import:MA10-2")
      (libsource (lib "eagle-import") (part "MA10-2"))
    )
    (comp (ref "JP4")
      (value "JP2E")
      (footprint "eagle-import:JP2")
      (libsource (lib "eagle-import") (part "JP2E"))
    )
    (comp (ref "R16")
      (value "1M")
      (footprint "eagle-import:R0805")
      (fields (field (name "PARTNO") "ERJ-6ENF1004V"))
      (libsource (lib "eagle-import") (part "R_0805"))
    )
    (comp (ref "R24")
      (value "91.0K")
      (footprint "eagle-import:R0805")
      (fields (field (name "PARTNO") "ERJ-6ENF9092V"))
      (libsource (lib "eagle-import") (part "R_0805"))
    )
    (comp (ref "R25")
      (value "10K")
      (footprint "eagle-import:R0805")
      (fields (field (name "PARTNO") "ERJ-6ENF1002V"))
      (libsource (lib "eagle-import") (part "R_0805"))
    )
    (comp (ref "R26")
      (value "10K")
      (footprint "eagle-import:EVME-SIDE")
      (fields (field (name "PARTNO") "EVM-EGGA00B14"))
      (libsource (lib "eagle-import") (part "TRIM_EU-EVME-SIDE"))
    )
    (comp (ref "R27")
      (value "10K")
      (footprint "eagle-import:EVME-SIDE")
      (fields (field (name "PARTNO") "EVM-EGGA00B14"))
      (libsource (lib "eagle-import") (part "TRIM_EU-EVME-SIDE"))
    )
    (comp (ref "R28")
      (value "10K")
      (footprint "eagle-import:R0805")
      (fields (field (name "PARTNO") "ERJ-6ENF1002V"))
      (libsource (lib "eagle-import") (part "R_0805"))
    )
    (comp (ref "R29")
      (value "332K")
      (footprint "eagle-import:R0805")
      (fields (field (name "PARTNO") "ERJ-6ENF3323V"))
      (libsource (lib "eagle-import") (part "R_0805"))
    )
    (comp (ref "R30")
      (value "4.75K")
      (footprint "eagle-import:R0805")
      (fields (field (name "PARTNO") "ERJ-6ENF4751V"))
      (libsource (lib "eagle-import") (part "R_0805"))
    )
    (comp (ref "R31")
      (value "22K")
      (footprint "eagle-import:R0805")
      (fields (field (name "PARTNO") "ERJ-6ENF2212V"))
      (libsource (lib "eagle-import") (part "R_0805"))
    )
    (comp (ref "R32")
      (value "301K")
      (footprint "eagle-import:R0805")
      (fields (field (name "PARTNO") "ERJ-6ENF3013V"))
      (libsource (lib "eagle-import") (part "R_0805"))
    )
    (comp (ref "R33")
      (value "4.75K")
      (footprint "eagle-import:R0805")
      (fields (field (name "PARTNO") "ERJ-6ENF4751V"))
      (libsource (lib "eagle-import") (part "R_0805"))
    )
    (comp (ref "R34")
      (value "100K")
      (footprint "eagle-import:R0805")
      (fields (field (name "PARTNO") "ERJ-6ENF1003V"))
      (libsource (lib "eagle-import") (part "R_0805"))
    )
    (comp (ref "R35")
      (value "150K")
      (footprint "eagle-import:R0805")
      (fields (field (name "PARTNO") "ERJ-6ENF1503V"))
      (libsource (lib "eagle-import") (part "R_0805"))
    )
    (comp (ref "R36")
      (value "5.62K")
      (footprint "eagle-import:R0805")
      (fields (field (name "PARTNO") "ERJ-6ENF5621V"))
      (libsource (lib "eagle-import") (part "R_0805"))
    )
    (comp (ref "R37")
      (value "100K")
      (footprint "eagle-import:R0805")
      (fields (field (name "PARTNO") "ERJ-6ENF1003V"))
      (libsource (lib "eagle-import") (part "R_0805"))
    )
    (comp (ref "R38")
      (value "8.25K")
      (footprint "eagle-import:R0805")
      (fields (field (name "PARTNO") "ERJ-6ENF8251V"))
      (libsource (lib "eagle-import") (part "R_0805"))
    )
    (comp (ref "R39")
      (value "10K")
      (footprint "eagle-import:R0805")
      (fields (field (name "PARTNO") "ERJ-6ENF1002V"))
      (libsource (lib "eagle-import") (part "R_0805"))
    )
    (comp (ref "R40")
      (value "10K")
      (footprint "eagle-import:R0805")
      (fields (field (name "PARTNO") "ERJ-6ENF1002V"))
      (libsource (lib "eagle-import") (part "R_0805"))
    )
    (comp (ref "R41")
      (value "100K")
      (footprint "eagle-import:R0805")
      (fields (field (name "PARTNO") "ERJ-6ENF1003V"))
      (libsource (lib "eagle-import") (part "R_0805"))
    )
    (comp (ref "R42")
      (value "11.3K")
      (footprint "eagle-import:R0805")
      (fields (field (name "PARTNO") "ERJ-6ENF1132V"))
      (libsource (lib "eagle-import") (part "R_0805"))
    )
    (comp (ref "R43")
      (value "10K")
      (footprint "eagle-import:R0805")
      (fields (field (name "PARTNO") "ERJ-6ENF1002V"))
      (libsource (lib "eagle-import") (part "R_0805"))
    )
    (comp (ref "R44")
      (value "22K")
      (footprint "eagle-import:R0805")
      (fields (field (name "PARTNO") "ERJ-6ENF2212V"))
      (libsource (lib "eagle-import") (part "R_0805"))
    )
    (comp (ref "R45")
      (value "100K")
      (footprint "eagle-import:R0805")
      (fields (field (name "PARTNO") "ERJ-6ENF1003V"))
      (libsource (lib "eagle-import") (part "R_0805"))
    )
    (comp (ref "R46")
      (value "1M")
      (footprint "eagle-import:R0805")
      (fields (field (name "PARTNO") "ERJ-6ENF1004V"))
      (libsource (lib "eagle-import") (part "R_0805"))
    )
    (comp (ref "R47")
      (value "93.1K")
      (footprint "eagle-import:R0805")
      (fields (field (name "PARTNO") "ERJ-6ENF9312V"))
      (libsource (lib "eagle-import") (part "R_0805"))
    )
    (comp (ref "R48")
      (value "22K")
      (footprint "eagle-import:R0805")
      (fields (field (name "PARTNO") "ERJ-6ENF2212V"))
      (libsource (lib "eagle-import") (part "R_0805"))
    )
    (comp (ref "R49")
      (value "100K")
      (footprint "eagle-import:R0805")
      (fields (field (name "PARTNO") "ERJ-6ENF1003V"))
      (libsource (lib "eagle-import") (part "R_0805"))
    )
    (comp (ref "R50")
      (value "10K")
      (footprint "eagle-import:R0805")
      (fields (field (name "PARTNO") "ERJ-6ENF1002V"))
      (libsource (lib "eagle-import") (part "R_0805"))
    )
    (comp (ref "R51")
      (value "22K")
      (footprint "eagle-import:R0805")
      (fields (field (name "PARTNO") "ERJ-6ENF2212V"))
      (libsource (lib "eagle-import") (part "R_0805"))
    )
    (comp (ref "R52")
      (value "200K")
      (footprint "eagle-import:EVME-SIDE")
      (fields (field (name "PARTNO") "EVM-EGGA00B25"))
      (libsource (lib "eagle-import") (part "TRIM_EU-EVME-SIDE"))
    )
    (comp (ref "R53")
      (value "33.2K")
      (footprint "eagle-import:R0805")
      (fields (field (name "PARTNO") "ERJ-6ENF3322V"))
      (libsource (lib "eagle-import") (part "R_0805"))
    )
    (comp (ref "R54")
      (value "10K")
      (footprint "eagle-import:R0805")
      (fields (field (name "PARTNO") "ERJ-6ENF1002V"))
      (libsource (lib "eagle-import") (part "R_0805"))
    )
    (comp (ref "R55")
      (value "1M")
      (footprint "eagle-import:R0805")
      (fields (field (name "PARTNO") "ERJ-6ENF1004V"))
      (libsource (lib "eagle-import") (part "R_0805"))
    )
    (comp (ref "R56")
      (value "10K")
      (footprint "eagle-import:R0805")
      (fields (field (name "PARTNO") "ERJ-6ENF1002V"))
      (libsource (lib "eagle-import") (part "R_0805"))
    )
    (comp (ref "R57")
      (value "10K")
      (footprint "eagle-import:R0805")
      (fields (field (name "PARTNO") "ERJ-6ENF1002V"))
      (libsource (lib "eagle-import") (part "R_0805"))
    )
    (comp (ref "R58")
      (value "10K")
      (footprint "eagle-import:R0805")
      (fields (field (name "PARTNO") "ERJ-6ENF1002V"))
      (libsource (lib "eagle-import") (part "R_0805"))
    )
    (comp (ref "R59")
      (value "22K")
      (footprint "eagle-import:R0805")
      (fields (field (name "PARTNO") "ERJ-6ENF2212V"))
      (libsource (lib "eagle-import") (part "R_0805"))
    )
    (comp (ref "R60")
      (value "33.2K")
      (footprint "eagle-import:R0805")
      (fields (field (name "PARTNO") "ERJ-6ENF3322V"))
      (libsource (lib "eagle-import") (part "R_0805"))
    )
    (comp (ref "R61")
      (value "100K")
      (footprint "eagle-import:R0805")
      (fields (field (name "PARTNO") "ERJ-6ENF1003V"))
      (libsource (lib "eagle-import") (part "R_0805"))
    )
    (comp (ref "R62")
      (value "1M")
      (footprint "eagle-import:R0805")
      (fields (field (name "PARTNO") "ERJ-6ENF1004V"))
      (libsource (lib "eagle-import") (part "R_0805"))
    )
    (comp (ref "R63")
      (value "10K")
      (footprint "eagle-import:EVME-SIDE")
      (fields (field (name "PARTNO") "EVM-EGGA00B14"))
      (libsource (lib "eagle-import") (part "TRIM_EU-EVME-SIDE"))
    )
    (comp (ref "R64")
      (value "22K")
      (footprint "eagle-import:R0805")
      (fields (field (name "PARTNO") "ERJ-6ENF2212V"))
      (libsource (lib "eagle-import") (part "R_0805"))
    )
    (comp (ref "R65")
      (value "10K")
      (footprint "eagle-import:R0805")
      (fields (field (name "PARTNO") "ERJ-6ENF1002V"))
      (libsource (lib "eagle-import") (part "R_0805"))
    )
    (comp (ref "R66")
      (value "10K")
      (footprint "eagle-import:EVM-L4G")
      (fields (field (name "PARTNO") "EVM-L4GA00B14"))
      (libsource (lib "eagle-import") (part "TRIM_EU-EVM-L4G"))
    )
    (comp (ref "R67")
      (value "10K")
      (footprint "eagle-import:R0805")
      (fields (field (name "PARTNO") "ERJ-6ENF1002V"))
      (libsource (lib "eagle-import") (part "R_0805"))
    )
    (comp (ref "R68")
      (value "100K")
      (footprint "eagle-import:R0805")
      (fields (field (name "PARTNO") "ERJ-6ENF1003V"))
      (libsource (lib "eagle-import") (part "R_0805"))
    )
    (comp (ref "R69")
      (value "10K")
      (footprint "eagle-import:R0805")
      (fields (field (name "PARTNO") "ERJ-6ENF1002V"))
      (libsource (lib "eagle-import") (part "R_0805"))
    )
    (comp (ref "R70")
      (value "10K")
      (footprint "eagle-import:R0805")
      (fields (field (name "PARTNO") "ERJ-6ENF1002V"))
      (libsource (lib "eagle-import") (part "R_0805"))
    )
    (comp (ref "R71")
      (value "10K")
      (footprint "eagle-import:EVME-SIDE")
      (fields (field (name "PARTNO") "EVM-EGGA00B14"))
      (libsource (lib "eagle-import") (part "TRIM_EU-EVME-SIDE"))
    )
    (comp (ref "R72")
      (value "22K")
      (footprint "eagle-import:R0805")
      (fields (field (name "PARTNO") "ERJ-6ENF2212V"))
      (libsource (lib "eagle-import") (part "R_0805"))
    )
    (comp (ref "R73")
      (value "100K")
      (footprint "eagle-import:R0805")
      (fields (field (name "PARTNO") "ERJ-6ENF1003V"))
      (libsource (lib "eagle-import") (part "R_0805"))
    )
    (comp (ref "R74")
      (value "100K")
      (footprint "eagle-import:R0805")
      (fields (field (name "PARTNO") "ERJ-6ENF1003V"))
      (libsource (lib "eagle-import") (part "R_0805"))
    )
    (comp (ref "R75")
      (value "10K")
      (footprint "eagle-import:EVME-SIDE")
      (fields (field (name "PARTNO") "EVM-EGGA00B14"))
      (libsource (lib "eagle-import") (part "TRIM_EU-EVME-SIDE"))
    )
    (comp (ref "R76")
      (value "22K")
      (footprint "eagle-import:R0805")
      (fields (field (name "PARTNO") "ERJ-6ENF2212V"))
      (libsource (lib "eagle-import") (part "R_0805"))
    )
    (comp (ref "R77")
      (value "100K")
      (footprint "eagle-import:R0805")
      (fields (field (name "PARTNO") "ERJ-6ENF1003V"))
      (libsource (lib "eagle-import") (part "R_0805"))
    )
    (comp (ref "R78")
      (value "100K")
      (footprint "eagle-import:R0805")
      (fields (field (name "PARTNO") "ERJ-6ENF1003V"))
      (libsource (lib "eagle-import") (part "R_0805"))
    )
    (comp (ref "R79")
      (value "10K")
      (footprint "eagle-import:R0805")
      (fields (field (name "PARTNO") "ERJ-6ENF1002V"))
      (libsource (lib "eagle-import") (part "R_0805"))
    )
    (comp (ref "R82")
      (value "1.00K")
      (footprint "eagle-import:R0805")
      (fields (field (name "PARTNO") "ERJ-6ENF1001V"))
      (libsource (lib "eagle-import") (part "R_0805"))
    )
    (comp (ref "R83")
      (value "1.00K")
      (footprint "eagle-import:R0805")
      (fields (field (name "PARTNO") "ERJ-6ENF1001V"))
      (libsource (lib "eagle-import") (part "R_0805"))
    )
    (comp (ref "TP3")
      (value "TPTP10SQ")
      (footprint "eagle-import:TP10SQ")
      (libsource (lib "eagle-import") (part "TPTP10SQ"))
    )
    (comp (ref "TP4")
      (value "TPTP10SQ")
      (footprint "eagle-import:TP10SQ")
      (libsource (lib "eagle-import") (part "TPTP10SQ"))
    )
    (comp (ref "TP5")
      (value "TPTP10SQ")
      (footprint "eagle-import:TP10SQ")
      (libsource (lib "eagle-import") (part "TPTP10SQ"))
    )
    (comp (ref "TP6")
      (value "TPTP10SQ")
      (footprint "eagle-import:TP10SQ")
      (libsource (lib "eagle-import") (part "TPTP10SQ"))
    )
    (comp (ref "TP7")
      (value "TPTP10SQ")
      (footprint "eagle-import:TP10SQ")
      (libsource (lib "eagle-import") (part "TPTP10SQ"))
    )
    (comp (ref "TP8")
      (value "TPS-SMD-10SN")
      (footprint "eagle-import:SMD-10SN")
      (libsource (lib "eagle-import") (part "TPS-SMD-10SN"))
    )
    (comp (ref "TP10")
      (value "TPS-SMD-10SN")
      (footprint "eagle-import:SMD-10SN")
      (fields (field (name "LABEL") "GND"))
      (libsource (lib "eagle-import") (part "TPS-SMD-10SN"))
    )
    (comp (ref "U5")
      (value "LM324D")
      (footprint "eagle-import:SO14")
      (fields (field (name "PARTNO") "LM324D"))
      (libsource (lib "eagle-import") (part "LM324D"))
    )
    (comp (ref "U6")
      (value "CM8870CS")
      (footprint "eagle-import:SO18W")
      (fields (field (name "PARTNO") "MT8870DS"))
      (libsource (lib "eagle-import") (part "CM8870CS"))
    )
    (comp (ref "U7")
      (value "MAX323CSA")
      (footprint "eagle-import:SO08")
      (fields (field (name "PARTNO") "MAX323CSA+"))
      (libsource (lib "eagle-import") (part "MAX323CSA"))
    )
    (comp (ref "U8")
      (value "MX828DS")
      (footprint "eagle-import:SSOP24")
      (fields (field (name "PARTNO") "MX828DW"))
      (libsource (lib "eagle-import") (part "MX828DS"))
    )
    (comp (ref "U9")
      (value "ISD4002S")
      (footprint "eagle-import:SO28W")
      (fields (field (name "PARTNO") "ISD4002-240SY"))
      (libsource (lib "eagle-import") (part "ISD4002S"))
    )
    (comp (ref "U10")
      (value "TL084D")
      (footprint "eagle-import:SO14")
      (fields (field (name "PARTNO") "TLC084CD"))
      (libsource (lib "eagle-import") (part "TL084D"))
    )
    (comp (ref "Y2")
      (value "3.579 MHZ")
      (footprint "eagle-import:TC310H")
      (fields (field (name "PARTNO") "ECS-35-18-10X"))
      (libsource (lib "eagle-import") (part "CRYTALTC310H"))
    )
    (comp (ref "Y3")
      (value "4.032MHZ")
      (footprint "eagle-import:SM49")
      (fields (field (name "PARTNO") "ECS-40.3-20-5PX-TR"))
      (libsource (lib "eagle-import") (part "CRYTALSM49"))
    )
  )
  (nets
    (net (code "1") (name "+2V5") (class "Default")
      (node (ref "R16") (pin "2") (pinfunction "2_2") (pintype "passive"))
      (node (ref "R46") (pin "2") (pinfunction "2_2") (pintype "passive"))
      (node (ref "R62") (pin "2") (pinfunction "2_2") (pintype "passive"))
      (node (ref "U10") (pin "1") (pinfunction "OUT_1") (pintype "output"))
      (node (ref "U10") (pin "2") (pinfunction "-IN_2") (pintype "input"))
    )
    (net (code "2") (name "+3V3") (class "Default")
      (node (ref "C21") (pin "+") (pinfunction "+_+") (pintype "passive"))
      (node (ref "C68") (pin "+") (pinfunction "+_+") (pintype "passive"))
      (node (ref "C69") (pin "1") (pinfunction "1_1") (pintype "passive"))
      (node (ref "C70") (pin "+") (pinfunction "+_+") (pintype "passive"))
      (node (ref "C71") (pin "1") (pinfunction "1_1") (pintype "passive"))
      (node (ref "TP2") (pin "TP") (pinfunction "TP_TP") (pintype "input"))
      (node (ref "U4") (pin "1") (pinfunction "OUT_1") (pintype "passive"))
      (node (ref "U9") (pin "18") (pinfunction "VCCA_18") (pintype "power_in"))
      (node (ref "U9") (pin "27") (pinfunction "VCCD_27") (pintype "power_in"))
    )
    (net (code "3") (name "+5V") (class "Default")
      (node (ref "C11") (pin "1") (pinfunction "1_1") (pintype "passive"))
      (node (ref "C22") (pin "1") (pinfunction "1_1") (pintype "passive"))
      (node (ref "C28") (pin "+") (pinfunction "+_+") (pintype "passive"))
      (node (ref "C30") (pin "2") (pinfunction "2_2") (pintype "passive"))
      (node (ref "C72") (pin "1") (pinfunction "1_1") (pintype "passive"))
      (node (ref "C73") (pin "1") (pinfunction "1_1") (pintype "passive"))
      (node (ref "C74") (pin "+") (pinfunction "+_+") (pintype "passive"))
      (node (ref "C9") (pin "1") (pinfunction "1_1") (pintype "passive"))
      (node (ref "D5") (pin "A") (pinfunction "A_A") (pintype "passive"))
      (node (ref "D9") (pin "C") (pinfunction "C_C") (pintype "passive"))
      (node (ref "J1") (pin "2") (pinfunction "VDD_2") (pintype "power_in"))
      (node (ref "J2") (pin "8") (pinfunction "8_8") (pintype "passive"))
      (node (ref "JP1") (pin "4") (pinfunction "4_4") (pintype "passive"))
      (node (ref "JP1") (pin "7") (pinfunction "7_7") (pintype "passive"))
      (node (ref "JP2") (pin "2") (pinfunction "2_2") (pintype "passive"))
      (node (ref "L3") (pin "2") (pinfunction "2_2") (pintype "passive"))
      (node (ref "R10") (pin "2") (pinfunction "2_2") (pintype "passive"))
      (node (ref "R11") (pin "2") (pinfunction "2_2") (pintype "passive"))
      (node (ref "R18") (pin "2") (pinfunction "2_2") (pintype "passive"))
      (node (ref "R2") (pin "1") (pinfunction "1_1") (pintype "passive"))
      (node (ref "R20") (pin "2") (pinfunction "2_2") (pintype "passive"))
      (node (ref "R50") (pin "1") (pinfunction "1_1") (pintype "passive"))
      (node (ref "R6") (pin "1") (pinfunction "1_1") (pintype "passive"))
      (node (ref "R69") (pin "2") (pinfunction "2_2") (pintype "passive"))
      (node (ref "R7") (pin "1") (pinfunction "1_1") (pintype "passive"))
      (node (ref "R70") (pin "2") (pinfunction "2_2") (pintype "passive"))
      (node (ref "R74") (pin "2") (pinfunction "2_2") (pintype "passive"))
      (node (ref "R79") (pin "2") (pinfunction "2_2") (pintype "passive"))
      (node (ref "RN1") (pin "5") (pinfunction "5_5") (pintype "passive"))
      (node (ref "RN1") (pin "6") (pinfunction "6_6") (pintype "passive"))
      (node (ref "RN1") (pin "7") (pinfunction "7_7") (pintype "passive"))
      (node (ref "RN1") (pin "8") (pinfunction "8_8") (pintype "passive"))
      (node (ref "TP1") (pin "TP") (pinfunction "TP_TP") (pintype "input"))
      (node (ref "U1") (pin "8") (pinfunction "VCC_8") (pintype "power_in"))
      (node (ref "U11") (pin "3") (pinfunction "OUT_3") (pintype "passive"))
      (node (ref "U3") (pin "22") (pinfunction "~{FORCEOFF}_22") (pintype "input"))
      (node (ref "U3") (pin "26") (pinfunction "VCC_26") (pintype "power_in"))
      (node (ref "U6") (pin "18") (pinfunction "VDD_18") (pintype "power_in"))
      (node (ref "U8") (pin "24") (pinfunction "VDD_24") (pintype "power_in"))
    )
    (net (code "4") (name "+12V") (class "Default")
      (node (ref "C25") (pin "1") (pinfunction "1_1") (pintype "passive"))
      (node (ref "C26") (pin "+") (pinfunction "+_+") (pintype "passive"))
      (node (ref "C27") (pin "+") (pinfunction "+_+") (pintype "passive"))
      (node (ref "C75") (pin "1") (pinfunction "1_1") (pintype "passive"))
      (node (ref "C76") (pin "1") (pinfunction "1_1") (pintype "passive"))
      (node (ref "C77") (pin "1") (pinfunction "1_1") (pintype "passive"))
      (node (ref "D5") (pin "C") (pinfunction "C_C") (pintype "passive"))
      (node (ref "D6") (pin "C") (pinfunction "C_C") (pintype "passive"))
      (node (ref "D8") (pin "C") (pinfunction "C_C") (pintype "passive"))
      (node (ref "J2") (pin "9") (pinfunction "9_9") (pintype "passive"))
      (node (ref "R21") (pin "2") (pinfunction "2_2") (pintype "passive"))
      (node (ref "R73") (pin "2") (pinfunction "2_2") (pintype "passive"))
      (node (ref "TP9") (pin "TP") (pinfunction "TP_TP") (pintype "input"))
      (node (ref "U10") (pin "4") (pinfunction "V+_4") (pintype "power_in"))
      (node (ref "U11") (pin "1") (pinfunction "IN_1") (pintype "input"))
      (node (ref "U4") (pin "3") (pinfunction "IN_3") (pintype "input"))
      (node (ref "U5") (pin "4") (pinfunction "V+_4") (pintype "power_in"))
      (node (ref "U7") (pin "8") (pinfunction "V+_8") (pintype "power_in"))
    )
    (net (code "6") (name "AGND") (class "Default")
      (node (ref "C19") (pin "2") (pinfunction "2_2") (pintype "passive"))
      (node (ref "C20") (pin "2") (pinfunction "2_2") (pintype "passive"))
      (node (ref "C38") (pin "1") (pinfunction "1_1") (pintype "passive"))
      (node (ref "C4") (pin "1") (pinfunction "1_1") (pintype "passive"))
      (node (ref "C55") (pin "-") (pinfunction "-_-") (pintype "passive"))
      (node (ref "C56") (pin "-") (pinfunction "-_-") (pintype "passive"))
      (node (ref "C57") (pin "2") (pinfunction "2_2") (pintype "passive"))
      (node (ref "C60") (pin "2") (pinfunction "2_2") (pintype "passive"))
      (node (ref "C62") (pin "2") (pinfunction "2_2") (pintype "passive"))
      (node (ref "C63") (pin "1") (pinfunction "1_1") (pintype "passive"))
      (node (ref "C65") (pin "2") (pinfunction "2_2") (pintype "passive"))
      (node (ref "C66") (pin "2") (pinfunction "2_2") (pintype "passive"))
      (node (ref "C67") (pin "-") (pinfunction "-_-") (pintype "passive"))
      (node (ref "C68") (pin "-") (pinfunction "-_-") (pintype "passive"))
      (node (ref "C69") (pin "2") (pinfunction "2_2") (pintype "passive"))
      (node (ref "C75") (pin "2") (pinfunction "2_2") (pintype "passive"))
      (node (ref "C76") (pin "2") (pinfunction "2_2") (pintype "passive"))
      (node (ref "C77") (pin "2") (pinfunction "2_2") (pintype "passive"))
      (node (ref "C78") (pin "-") (pinfunction "-_-") (pintype "passive"))
      (node (ref "C79") (pin "-") (pinfunction "-_-") (pintype "passive"))
      (node (ref "C8") (pin "2") (pinfunction "2_2") (pintype "passive"))
      (node (ref "D10") (pin "A") (pinfunction "A_A") (pintype "passive"))
      (node (ref "D7") (pin "A") (pinfunction "A_A") (pintype "passive"))
      (node (ref "J2") (pin "7") (pinfunction "7_7") (pintype "passive"))
      (node (ref "R22") (pin "1") (pinfunction "1_1") (pintype "passive"))
      (node (ref "R23") (pin "1") (pinfunction "1_1") (pintype "passive"))
      (node (ref "R26") (pin "1") (pinfunction "1_1") (pintype "passive"))
      (node (ref "R27") (pin "1") (pinfunction "1_1") (pintype "passive"))
      (node (ref "R33") (pin "1") (pinfunction "1_1") (pintype "passive"))
      (node (ref "R37") (pin "2") (pinfunction "2_2") (pintype "passive"))
      (node (ref "R38") (pin "2") (pinfunction "2_2") (pintype "passive"))
      (node (ref "R39") (pin "2") (pinfunction "2_2") (pintype "passive"))
      (node (ref "R40") (pin "2") (pinfunction "2_2") (pintype "passive"))
      (node (ref "R49") (pin "1") (pinfunction "1_1") (pintype "passive"))
      (node (ref "R61") (pin "1") (pinfunction "1_1") (pintype "passive"))
      (node (ref "R63") (pin "1") (pinfunction "1_1") (pintype "passive"))
      (node (ref "R66") (pin "1") (pinfunction "1_1") (pintype "passive"))
      (node (ref "R67") (pin "2") (pinfunction "2_2") (pintype "passive"))
      (node (ref "R71") (pin "1") (pinfunction "1_1") (pintype "passive"))
      (node (ref "R75") (pin "1") (pinfunction "1_1") (pintype "passive"))
      (node (ref "R77") (pin "1") (pinfunction "1_1") (pintype "passive"))
      (node (ref "R78") (pin "1") (pinfunction "1_1") (pintype "passive"))
      (node (ref "R80") (pin "2") (pinfunction "2_2") (pintype "passive"))
      (node (ref "TP10") (pin "TP") (pinfunction "TP_TP") (pintype "passive"))
      (node (ref "U10") (pin "11") (pinfunction "V-_11") (pintype "power_in"))
      (node (ref "U12") (pin "2") (pinfunction "GND_2") (pintype "input"))
      (node (ref "U5") (pin "11") (pinfunction "V-_11") (pintype "power_in"))
      (node (ref "U7") (pin "4") (pinfunction "V-_4") (pintype "power_in"))
      (node (ref "U9") (pin "11") (pinfunction "VSSA_11") (pintype "power_in"))
      (node (ref "U9") (pin "12") (pinfunction "VSSA_12") (pintype "power_in"))
      (node (ref "U9") (pin "23") (pinfunction "VSSA_23") (pintype "power_in"))
      (node (ref "X3") (pin "5") (pinfunction "5_5") (pintype "passive"))
      (node (ref "X4") (pin "5") (pinfunction "5_5") (pintype "passive"))
    )
    (net (code "7") (name "AUX_AUDIO") (class "Default")
      (node (ref "C45") (pin "2") (pinfunction "2_2") (pintype "passive"))
      (node (ref "J2") (pin "3") (pinfunction "3_3") (pintype "passive"))
      (node (ref "R49") (pin "2") (pinfunction "2_2") (pintype "passive"))
      (node (ref "X3") (pin "8") (pinfunction "8_8") (pintype "passive"))
      (node (ref "X4") (pin "8") (pinfunction "8_8") (pintype "passive"))
    )
    (net (code "8") (name "AUX_AUDIO_OUT") (class "Default")
      (node (ref "TP4") (pin "TP") (pinfunction "TP_TP") (pintype "input"))
      (node (ref "U7") (pin "1") (pinfunction "NO_1") (pintype "passive"))
      (node (ref "U8") (pin "22") (pinfunction "MOD1_22") (pintype "output"))
    )
    (net (code "9") (name "AVR_5V") (class "Default")
      (node (ref "C1") (pin "1") (pinfunction "1_1") (pintype "passive"))
      (node (ref "C2") (pin "1") (pinfunction "1_1") (pintype "passive"))
      (node (ref "D1") (pin "C") (pinfunction "C_C") (pintype "passive"))
      (node (ref "L2") (pin "2") (pinfunction "2_2") (pintype "passive"))
      (node (ref "R5") (pin "2") (pinfunction "2_2") (pintype "passive"))
      (node (ref "U2") (pin "21") (pinfunction "VCC_21") (pintype "power_in"))
      (node (ref "U2") (pin "52") (pinfunction "VCC1_52") (pintype "power_in"))
    )
    (net (code "10") (name "AVR_REF") (class "Default")
      (node (ref "C4") (pin "2") (pinfunction "2_2") (pintype "passive"))
      (node (ref "U12") (pin "1") (pinfunction "OUT_1") (pintype "passive"))
      (node (ref "U2") (pin "64") (pinfunction "AVCC_64") (pintype "bidirectional"))
    )
    (net (code "11") (name "BEEP_PWM") (class "Default")
      (node (ref "R68") (pin "1") (pinfunction "1_1") (pintype "passive"))
      (node (ref "TP7") (pin "TP") (pinfunction "TP_TP") (pintype "input"))
      (node (ref "U2") (pin "15") (pinfunction "(OC1A/PCINT5)PB5_15") (pintype "bidirectional"))
    )
    (net (code "12") (name "B_CTS") (class "Default")
      (node (ref "U3") (pin "6") (pinfunction "R3IN_6") (pintype "input"))
      (node (ref "X2") (pin "8") (pinfunction "8_8") (pintype "passive"))
    )
    (net (code "13") (name "B_DCD") (class "Default")
      (node (ref "U3") (pin "8") (pinfunction "R5IN_8") (pintype "input"))
      (node (ref "X2") (pin "1") (pinfunction "1_1") (pintype "passive"))
    )
    (net (code "14") (name "B_DSR") (class "Default")
      (node (ref "U3") (pin "7") (pinfunction "R4IN_7") (pintype "input"))
      (node (ref "X2") (pin "6") (pinfunction "6_6") (pintype "passive"))
    )
    (net (code "15") (name "B_DTR") (class "Default")
      (node (ref "U3") (pin "10") (pinfunction "T2OUT_10") (pintype "output"))
      (node (ref "X2") (pin "4") (pinfunction "4_4") (pintype "passive"))
    )
    (net (code "16") (name "B_RI") (class "Default")
      (node (ref "U3") (pin "4") (pinfunction "R1IN_4") (pintype "input"))
      (node (ref "X2") (pin "9") (pinfunction "9_9") (pintype "passive"))
    )
    (net (code "17") (name "B_RTS") (class "Default")
      (node (ref "U3") (pin "11") (pinfunction "T3OUT_11") (pintype "output"))
      (node (ref "X2") (pin "7") (pinfunction "7_7") (pintype "passive"))
    )
    (net (code "18") (name "B_RXD") (class "Default")
      (node (ref "U3") (pin "5") (pinfunction "R2IN_5") (pintype "input"))
      (node (ref "X2") (pin "2") (pinfunction "2_2") (pintype "passive"))
    )
    (net (code "19") (name "B_TXD") (class "Default")
      (node (ref "U3") (pin "9") (pinfunction "T1OUT_9") (pintype "output"))
      (node (ref "X2") (pin "3") (pinfunction "3_3") (pintype "passive"))
    )
    (net (code "20") (name "CGND") (class "Default")
      (node (ref "C23") (pin "2") (pinfunction "2_2") (pintype "passive"))
      (node (ref "C24") (pin "2") (pinfunction "2_2") (pintype "passive"))
      (node (ref "C25") (pin "2") (pinfunction "2_2") (pintype "passive"))
      (node (ref "C26") (pin "-") (pinfunction "-_-") (pintype "passive"))
      (node (ref "C27") (pin "-") (pinfunction "-_-") (pintype "passive"))
      (node (ref "C28") (pin "-") (pinfunction "-_-") (pintype "passive"))
      (node (ref "C80") (pin "2") (pinfunction "2_2") (pintype "passive"))
      (node (ref "D8") (pin "A") (pinfunction "A_A") (pintype "passive"))
      (node (ref "D9") (pin "A") (pinfunction "A_A") (pintype "passive"))
      (node (ref "L1") (pin "4") (pinfunction "4_4") (pintype "passive"))
      (node (ref "Q3") (pin "3") (pinfunction "S_3") (pintype "passive"))
      (node (ref "Q4") (pin "3") (pinfunction "S_3") (pintype "passive"))
      (node (ref "R13") (pin "2") (pinfunction "2_2") (pintype "passive"))
      (node (ref "R80") (pin "1") (pinfunction "1_1") (pintype "passive"))
      (node (ref "R81") (pin "1") (pinfunction "1_1") (pintype "passive"))
      (node (ref "U11") (pin "2") (pinfunction "GND_2") (pintype "input"))
      (node (ref "X3") (pin "4") (pinfunction "4_4") (pintype "passive"))
      (node (ref "X4") (pin "4") (pinfunction "4_4") (pintype "passive"))
    )
    (net (code "21") (name "COM_CTS") (class "Default")
      (node (ref "U2") (pin "14") (pinfunction "(OC2A/PCINT4)PB4_14") (pintype "bidirectional"))
      (node (ref "U3") (pin "17") (pinfunction "R3OUT_17") (pintype "output"))
    )
    (net (code "22") (name "COM_DCD") (class "Default")
      (node (ref "U2") (pin "8") (pinfunction "(T3/INT6)PE6_8") (pintype "bidirectional"))
      (node (ref "U3") (pin "15") (pinfunction "R5OUT_15") (pintype "output"))
    )
    (net (code "23") (name "COM_DSR") (class "Default")
      (node (ref "U2") (pin "17") (pinfunction "(OC0A/OC1C/PCINT7)PB7_17") (pintype "bidirectional"))
      (node (ref "U3") (pin "16") (pinfunction "R4OUT_16") (pintype "output"))
    )
    (net (code "24") (name "COM_DTR") (class "Default")
      (node (ref "U2") (pin "35") (pinfunction "(A8)PC0_35") (pintype "output"))
      (node (ref "U3") (pin "12") (pinfunction "T3IN_12") (pintype "input"))
      (node (ref "U3") (pin "13") (pinfunction "T2IN_13") (pintype "input"))
    )
    (net (code "25") (name "COM_RXD") (class "Default")
      (node (ref "R3") (pin "2") (pinfunction "2_2") (pintype "passive"))
      (node (ref "U2") (pin "2") (pinfunction "(RXD0/PCINT8/PDI)PE0_2") (pintype "bidirectional"))
      (node (ref "U3") (pin "18") (pinfunction "R2OUT_18") (pintype "output"))
    )
    (net (code "26") (name "COM_TXD") (class "Default")
      (node (ref "R1") (pin "2") (pinfunction "2_2") (pintype "passive"))
      (node (ref "U2") (pin "3") (pinfunction "(TXD0/PDO)PE1_3") (pintype "bidirectional"))
      (node (ref "U3") (pin "14") (pinfunction "T1IN_14") (pintype "input"))
    )
    (net (code "27") (name "COS") (class "Default")
      (node (ref "R13") (pin "1") (pinfunction "1_1") (pintype "passive"))
      (node (ref "R19") (pin "2") (pinfunction "2_2") (pintype "passive"))
      (node (ref "X3") (pin "3") (pinfunction "3_3") (pintype "passive"))
      (node (ref "X4") (pin "3") (pinfunction "3_3") (pintype "passive"))
    )
    (net (code "28") (name "CS_DTMF") (class "Default")
      (node (ref "U2") (pin "38") (pinfunction "(A11)PC3_38") (pintype "output"))
      (node (ref "U6") (pin "10") (pinfunction "TOE_10") (pintype "input"))
    )
    (net (code "29") (name "DISC_AUDIO") (class "Default")
      (node (ref "R26") (pin "3") (pinfunction "3_3") (pintype "passive"))
      (node (ref "R27") (pin "3") (pinfunction "3_3") (pintype "passive"))
      (node (ref "X3") (pin "6") (pinfunction "6_6") (pintype "passive"))
      (node (ref "X4") (pin "6") (pinfunction "6_6") (pintype "passive"))
    )
    (net (code "30") (name "DTMF_Q1") (class "Default")
      (node (ref "U2") (pin "29") (pinfunction "(ICP1)PD4_29") (pintype "bidirectional"))
      (node (ref "U6") (pin "11") (pinfunction "Q1_11") (pintype "output"))
    )
    (net (code "31") (name "DTMF_Q2") (class "Default")
      (node (ref "U2") (pin "30") (pinfunction "(XCK1)PD5_30") (pintype "bidirectional"))
      (node (ref "U6") (pin "12") (pinfunction "Q2_12") (pintype "output"))
    )
    (net (code "32") (name "DTMF_Q3") (class "Default")
      (node (ref "U2") (pin "31") (pinfunction "(T1)PD6_31") (pintype "bidirectional"))
      (node (ref "U6") (pin "13") (pinfunction "Q3_13") (pintype "output"))
    )
    (net (code "33") (name "DTMF_Q4") (class "Default")
      (node (ref "U2") (pin "32") (pinfunction "(T2)PD7_32") (pintype "bidirectional"))
      (node (ref "U6") (pin "14") (pinfunction "Q4_14") (pintype "output"))
    )
    (net (code "34") (name "EXP_IO0") (class "Default")
      (node (ref "J2") (pin "15") (pinfunction "15_15") (pintype "passive"))
      (node (ref "U2") (pin "4") (pinfunction "(XCK0/AIN0)PE2_4") (pintype "bidirectional"))
    )
    (net (code "35") (name "EXP_IO1") (class "Default")
      (node (ref "J2") (pin "19") (pinfunction "19_19") (pintype "passive"))
      (node (ref "U2") (pin "5") (pinfunction "(OC3A/AIN1)PE3_5") (pintype "bidirectional"))
    )
    (net (code "36") (name "EXP_IO2") (class "Default")
      (node (ref "J2") (pin "17") (pinfunction "17_17") (pintype "passive"))
      (node (ref "U2") (pin "37") (pinfunction "(A10)PC2_37") (pintype "output"))
    )
    (net (code "37") (name "EXT_COS") (class "Default")
      (node (ref "Q5") (pin "3") (pinfunction "C_3") (pintype "passive"))
      (node (ref "R18") (pin "1") (pinfunction "1_1") (pintype "passive"))
      (node (ref "U2") (pin "34") (pinfunction "PG1(RD#)_34") (pintype "bidirectional"))
    )
    (net (code "38") (name "FAN") (class "Default")
      (node (ref "Q4") (pin "2") (pinfunction "D_2") (pintype "passive"))
      (node (ref "X3") (pin "2") (pinfunction "2_2") (pintype "passive"))
      (node (ref "X4") (pin "2") (pinfunction "2_2") (pintype "passive"))
    )
    (net (code "39") (name "FAN_DRIVE") (class "Default")
      (node (ref "R17") (pin "1") (pinfunction "1_1") (pintype "passive"))
      (node (ref "U2") (pin "39") (pinfunction "(A12)PC4_39") (pintype "output"))
    )
    (net (code "40") (name "GND") (class "Default")
      (node (ref "B1") (pin "-") (pinfunction "-_-") (pintype "passive"))
      (node (ref "C1") (pin "2") (pinfunction "2_2") (pintype "passive"))
      (node (ref "C12") (pin "1") (pinfunction "1_1") (pintype "passive"))
      (node (ref "C2") (pin "2") (pinfunction "2_2") (pintype "passive"))
      (node (ref "C21") (pin "-") (pinfunction "-_-") (pintype "passive"))
      (node (ref "C22") (pin "2") (pinfunction "2_2") (pintype "passive"))
      (node (ref "C3") (pin "-") (pinfunction "-_-") (pintype "passive"))
      (node (ref "C5") (pin "2") (pinfunction "2_2") (pintype "passive"))
      (node (ref "C53") (pin "2") (pinfunction "2_2") (pintype "passive"))
      (node (ref "C54") (pin "2") (pinfunction "2_2") (pintype "passive"))
      (node (ref "C6") (pin "2") (pinfunction "2_2") (pintype "passive"))
      (node (ref "C7") (pin "2") (pinfunction "2_2") (pintype "passive"))
      (node (ref "C70") (pin "-") (pinfunction "-_-") (pintype "passive"))
      (node (ref "C71") (pin "2") (pinfunction "2_2") (pintype "passive"))
      (node (ref "C72") (pin "2") (pinfunction "2_2") (pintype "passive"))
      (node (ref "C73") (pin "2") (pinfunction "2_2") (pintype "passive"))
      (node (ref "C74") (pin "-") (pinfunction "-_-") (pintype "passive"))
      (node (ref "C9") (pin "2") (pinfunction "2_2") (pintype "passive"))
      (node (ref "D2") (pin "A") (pinfunction "A_A") (pintype "passive"))
      (node (ref "J1") (pin "1") (pinfunction "VSS_1") (pintype "power_in"))
      (node (ref "J2") (pin "6") (pinfunction "6_6") (pintype "passive"))
      (node (ref "JP1") (pin "10") (pinfunction "10_10") (pintype "passive"))
      (node (ref "JP1") (pin "2") (pinfunction "2_2") (pintype "passive"))
      (node (ref "JP2") (pin "6") (pinfunction "6_6") (pintype "passive"))
      (node (ref "JP5") (pin "1") (pinfunction "1_1") (pintype "passive"))
      (node (ref "JP5") (pin "3") (pinfunction "3_3") (pintype "passive"))
      (node (ref "Q1") (pin "2") (pinfunction "E_2") (pintype "passive"))
      (node (ref "Q2") (pin "3") (pinfunction "S_3") (pintype "passive"))
      (node (ref "Q5") (pin "2") (pinfunction "E_2") (pintype "passive"))
      (node (ref "R2") (pin "3") (pinfunction "3_3") (pintype "passive"))
      (node (ref "R81") (pin "2") (pinfunction "2_2") (pintype "passive"))
      (node (ref "U1") (pin "4") (pinfunction "GND_4") (pintype "power_in"))
      (node (ref "U2") (pin "22") (pinfunction "GND_22") (pintype "power_in"))
      (node (ref "U2") (pin "53") (pinfunction "GND1_53") (pintype "power_in"))
      (node (ref "U2") (pin "63") (pinfunction "GND2_63") (pintype "power_in"))
      (node (ref "U3") (pin "23") (pinfunction "FORCEON_23") (pintype "input"))
      (node (ref "U3") (pin "25") (pinfunction "GND_25") (pintype "power_in"))
      (node (ref "U4") (pin "2") (pinfunction "GND_2") (pintype "input"))
      (node (ref "U4") (pin "4") (pinfunction "GND1_4") (pintype "input"))
      (node (ref "U6") (pin "5") (pinfunction "INH_5") (pintype "input"))
      (node (ref "U6") (pin "6") (pinfunction "PD_6") (pintype "input"))
      (node (ref "U6") (pin "9") (pinfunction "VSS_9") (pintype "power_in"))
      (node (ref "U8") (pin "12") (pinfunction "VSS_12") (pintype "power_in"))
      (node (ref "U9") (pin "26") (pinfunction "XCLK_26") (pintype "input"))
      (node (ref "U9") (pin "4") (pinfunction "VSSD_4") (pintype "power_in"))
      (node (ref "X2") (pin "5") (pinfunction "5_5") (pintype "passive"))
      (node (ref "X2") (pin "G1") (pinfunction "G1_G1") (pintype "passive"))
      (node (ref "X2") (pin "G2") (pinfunction "G2_G2") (pintype "passive"))
    )
    (net (code "41") (name "I2C_SCL") (class "Default")
      (node (ref "J2") (pin "13") (pinfunction "13_13") (pintype "passive"))
      (node (ref "R10") (pin "1") (pinfunction "1_1") (pintype "passive"))
      (node (ref "U1") (pin "6") (pinfunction "SCL_6") (pintype "bidirectional"))
      (node (ref "U2") (pin "25") (pinfunction "(SCL/INT0)PD0_25") (pintype "bidirectional"))
    )
    (net (code "42") (name "I2C_SDA") (class "Default")
      (node (ref "J2") (pin "11") (pinfunction "11_11") (pintype "passive"))
      (node (ref "R11") (pin "1") (pinfunction "1_1") (pintype "passive"))
      (node (ref "U1") (pin "5") (pinfunction "SDA_5") (pintype "bidirectional"))
      (node (ref "U2") (pin "26") (pinfunction "(SDA/INT1)PD1_26") (pintype "bidirectional"))
    )
    (net (code "43") (name "INT_DTMF") (class "Default")
      (node (ref "U2") (pin "6") (pinfunction "(OC3B/INT4)PE4_6") (pintype "bidirectional"))
      (node (ref "U6") (pin "15") (pinfunction "STD_15") (pintype "input"))
    )
    (net (code "44") (name "INT_EXP") (class "Default")
      (node (ref "J2") (pin "18") (pinfunction "18_18") (pintype "passive"))
      (node (ref "R79") (pin "1") (pinfunction "1_1") (pintype "passive"))
      (node (ref "U2") (pin "27") (pinfunction "(RXD1/INT2)PD2_27") (pintype "bidirectional"))
    )
    (net (code "45") (name "INT_ISD") (class "Default")
      (node (ref "R69") (pin "1") (pinfunction "1_1") (pintype "passive"))
      (node (ref "U2") (pin "7") (pinfunction "(OC3C/INT5)PE5_7") (pintype "bidirectional"))
      (node (ref "U9") (pin "25") (pinfunction "~{INT}_25") (pintype "output"))
    )
    (net (code "46") (name "INT_MX828") (class "Default")
      (node (ref "R50") (pin "2") (pinfunction "2_2") (pintype "passive"))
      (node (ref "U2") (pin "28") (pinfunction "(TXD1/INT3)PD3_28") (pintype "bidirectional"))
      (node (ref "U8") (pin "7") (pinfunction "~{IRQ}_7") (pintype "output"))
    )
    (net (code "47") (name "INT_RAC") (class "Default")
      (node (ref "R70") (pin "1") (pinfunction "1_1") (pintype "passive"))
      (node (ref "U2") (pin "9") (pinfunction "(ICP3/CLKO/INT7)PE7_9") (pintype "bidirectional"))
      (node (ref "U9") (pin "24") (pinfunction "RAC_24") (pintype "output"))
    )
    (net (code "48") (name "LCD_BKLITE") (class "Default")
      (node (ref "R9") (pin "1") (pinfunction "1_1") (pintype "passive"))
      (node (ref "U2") (pin "1") (pinfunction "PG5(OC0B)_1") (pintype "bidirectional"))
    )
    (net (code "49") (name "LCD_E") (class "Default")
      (node (ref "J1") (pin "6") (pinfunction "E_6") (pintype "input"))
      (node (ref "U2") (pin "41") (pinfunction "(A14)PC6_41") (pintype "output"))
    )
    (net (code "50") (name "LCD_RS") (class "Default")
      (node (ref "J1") (pin "4") (pinfunction "RS_4") (pintype "input"))
      (node (ref "U2") (pin "40") (pinfunction "(A13)PC5_40") (pintype "output"))
    )
    (net (code "51") (name "LCD_RW") (class "Default")
      (node (ref "J1") (pin "5") (pinfunction "R/W_5") (pintype "input"))
      (node (ref "U2") (pin "42") (pinfunction "(A15)PC7_42") (pintype "output"))
    )
    (net (code "52") (name "LED_PWR") (class "Default")
      (node (ref "R8") (pin "1") (pinfunction "1_1") (pintype "passive"))
      (node (ref "U2") (pin "43") (pinfunction "PG2(ALE)_43") (pintype "bidirectional"))
    )
    (net (code "53") (name "MIX_BUSS") (class "Default")
      (node (ref "C51") (pin "1") (pinfunction "1_1") (pintype "passive"))
      (node (ref "R51") (pin "2") (pinfunction "2_2") (pintype "passive"))
      (node (ref "R59") (pin "2") (pinfunction "2_2") (pintype "passive"))
      (node (ref "R64") (pin "2") (pinfunction "2_2") (pintype "passive"))
      (node (ref "R72") (pin "1") (pinfunction "1_1") (pintype "passive"))
      (node (ref "R76") (pin "2") (pinfunction "2_2") (pintype "passive"))
    )
    (net (code "54") (name "MIX_INSERT") (class "Default")
      (node (ref "C47") (pin "1") (pinfunction "1_1") (pintype "passive"))
      (node (ref "J2") (pin "4") (pinfunction "4_4") (pintype "passive"))
      (node (ref "R16") (pin "1") (pinfunction "1_1") (pintype "passive"))
    )
    (net (code "55") (name "MUTE_AUX") (class "Default")
      (node (ref "U2") (pin "18") (pinfunction "PG3(TOSC2)_18") (pintype "bidirectional"))
      (node (ref "U7") (pin "7") (pinfunction "IN_7") (pintype "input"))
    )
    (net (code "56") (name "MUTE_RX") (class "Default")
      (node (ref "U2") (pin "19") (pinfunction "PG4(TOSC1)_19") (pintype "bidirectional"))
      (node (ref "U7") (pin "3") (pinfunction "IN_3") (pintype "input"))
    )
    (net (code "57") (name "Net-(C24-Pad1)") (class "Default")
      (node (ref "C24") (pin "1") (pinfunction "1_1") (pintype "passive"))
      (node (ref "D6") (pin "A") (pinfunction "A_A") (pintype "passive"))
      (node (ref "L4") (pin "2") (pinfunction "2_2") (pintype "passive"))
    )
    (net (code "58") (name "Net-(C31-Pad1)") (class "Default")
      (node (ref "C31") (pin "1") (pinfunction "1_1") (pintype "passive"))
      (node (ref "R27") (pin "2") (pinfunction "2_2") (pintype "passive"))
    )
    (net (code "59") (name "Net-(C31-Pad2)") (class "Default")
      (node (ref "C31") (pin "2") (pinfunction "2_2") (pintype "passive"))
      (node (ref "R28") (pin "1") (pinfunction "1_1") (pintype "passive"))
    )
    (net (code "60") (name "Net-(C32-Pad2)") (class "Default")
      (node (ref "C32") (pin "2") (pinfunction "2_2") (pintype "passive"))
      (node (ref "C33") (pin "1") (pinfunction "1_1") (pintype "passive"))
      (node (ref "R33") (pin "2") (pinfunction "2_2") (pintype "passive"))
    )
    (net (code "61") (name "Net-(C33-Pad2)") (class "Default")
      (node (ref "C33") (pin "2") (pinfunction "2_2") (pintype "passive"))
      (node (ref "C34") (pin "1") (pinfunction "1_1") (pintype "passive"))
      (node (ref "R36") (pin "1") (pinfunction "1_1") (pintype "passive"))
    )
    (net (code "62") (name "Net-(C35-Pad1)") (class "Default")
      (node (ref "C35") (pin "1") (pinfunction "1_1") (pintype "passive"))
      (node (ref "R30") (pin "1") (pinfunction "1_1") (pintype "passive"))
    )
    (net (code "63") (name "Net-(C39-Pad1)") (class "Default")
      (node (ref "C39") (pin "1") (pinfunction "1_1") (pintype "passive"))
      (node (ref "R43") (pin "2") (pinfunction "2_2") (pintype "passive"))
    )
    (net (code "64") (name "Net-(C39-Pad2)") (class "Default")
      (node (ref "C39") (pin "2") (pinfunction "2_2") (pintype "passive"))
      (node (ref "R26") (pin "2") (pinfunction "2_2") (pintype "passive"))
    )
    (net (code "65") (name "Net-(C41-Pad2)") (class "Default")
      (node (ref "C41") (pin "2") (pinfunction "2_2") (pintype "passive"))
      (node (ref "JP4") (pin "3") (pinfunction "3_3") (pintype "passive"))
    )
    (net (code "66") (name "Net-(C43-Pad2)") (class "Default")
      (node (ref "C43") (pin "2") (pinfunction "2_2") (pintype "passive"))
      (node (ref "R45") (pin "1") (pinfunction "1_1") (pintype "passive"))
    )
    (net (code "67") (name "Net-(C44-Pad2)") (class "Default")
      (node (ref "C44") (pin "2") (pinfunction "2_2") (pintype "passive"))
      (node (ref "R48") (pin "1") (pinfunction "1_1") (pintype "passive"))
    )
    (net (code "68") (name "Net-(C45-Pad1)") (class "Default")
      (node (ref "C45") (pin "1") (pinfunction "1_1") (pintype "passive"))
      (node (ref "R82") (pin "2") (pinfunction "2_2") (pintype "passive"))
    )
    (net (code "69") (name "Net-(C47-Pad2)") (class "Default")
      (node (ref "C47") (pin "2") (pinfunction "2_2") (pintype "passive"))
      (node (ref "R51") (pin "1") (pinfunction "1_1") (pintype "passive"))
    )
    (net (code "70") (name "Net-(C48-Pad2)") (class "Default")
      (node (ref "C48") (pin "2") (pinfunction "2_2") (pintype "passive"))
      (node (ref "R56") (pin "1") (pinfunction "1_1") (pintype "passive"))
    )
    (net (code "71") (name "Net-(C50-Pad2)") (class "Default")
      (node (ref "C50") (pin "2") (pinfunction "2_2") (pintype "passive"))
      (node (ref "R59") (pin "1") (pinfunction "1_1") (pintype "passive"))
    )
    (net (code "72") (name "Net-(C51-Pad2)") (class "Default")
      (node (ref "C51") (pin "2") (pinfunction "2_2") (pintype "passive"))
      (node (ref "R60") (pin "1") (pinfunction "1_1") (pintype "passive"))
    )
    (net (code "73") (name "Net-(C52-Pad1)") (class "Default")
      (node (ref "C52") (pin "1") (pinfunction "1_1") (pintype "passive"))
      (node (ref "R83") (pin "2") (pinfunction "2_2") (pintype "passive"))
    )
    (net (code "74") (name "Net-(C58-Pad2)") (class "Default")
      (node (ref "C58") (pin "2") (pinfunction "2_2") (pintype "passive"))
      (node (ref "R63") (pin "3") (pinfunction "3_3") (pintype "passive"))
      (node (ref "R66") (pin "3") (pinfunction "3_3") (pintype "passive"))
    )
    (net (code "75") (name "Net-(C59-Pad1)") (class "Default")
      (node (ref "C59") (pin "1") (pinfunction "1_1") (pintype "passive"))
      (node (ref "C60") (pin "1") (pinfunction "1_1") (pintype "passive"))
      (node (ref "R65") (pin "1") (pinfunction "1_1") (pintype "passive"))
      (node (ref "R67") (pin "1") (pinfunction "1_1") (pintype "passive"))
      (node (ref "TP8") (pin "TP") (pinfunction "TP_TP") (pintype "passive"))
    )
    (net (code "76") (name "Net-(C61-Pad1)") (class "Default")
      (node (ref "C61") (pin "1") (pinfunction "1_1") (pintype "passive"))
      (node (ref "R68") (pin "2") (pinfunction "2_2") (pintype "passive"))
    )
    (net (code "77") (name "Net-(C61-Pad2)") (class "Default")
      (node (ref "C61") (pin "2") (pinfunction "2_2") (pintype "passive"))
      (node (ref "C62") (pin "1") (pinfunction "1_1") (pintype "passive"))
      (node (ref "R71") (pin "3") (pinfunction "3_3") (pintype "passive"))
    )
    (net (code "78") (name "Net-(C64-Pad2)") (class "Default")
      (node (ref "C64") (pin "2") (pinfunction "2_2") (pintype "passive"))
      (node (ref "R75") (pin "3") (pinfunction "3_3") (pintype "passive"))
    )
    (net (code "79") (name "Net-(C80-Pad1)") (class "Default")
      (node (ref "C80") (pin "1") (pinfunction "1_1") (pintype "passive"))
      (node (ref "L1") (pin "3") (pinfunction "3_3") (pintype "passive"))
      (node (ref "PF1") (pin "1") (pinfunction "1_1") (pintype "passive"))
    )
    (net (code "80") (name "Net-(D11-C)") (class "Default")
      (node (ref "D11") (pin "K") (pinfunction "C_K") (pintype "passive"))
      (node (ref "Q1") (pin "3") (pinfunction "C_3") (pintype "passive"))
    )
    (net (code "81") (name "Net-(D11-PadA)") (class "Default")
      (node (ref "D11") (pin "A") (pinfunction "A_A") (pintype "passive"))
      (node (ref "R7") (pin "2") (pinfunction "2_2") (pintype "passive"))
    )
    (net (code "82") (name "Net-(J1-VEE)") (class "Default")
      (node (ref "J1") (pin "3") (pinfunction "VEE_3") (pintype "power_in"))
      (node (ref "R2") (pin "2") (pinfunction "2_2") (pintype "passive"))
    )
    (net (code "83") (name "Net-(JP2-Pad1)") (class "Default")
      (node (ref "JP2") (pin "1") (pinfunction "1_1") (pintype "passive"))
      (node (ref "R1") (pin "1") (pinfunction "1_1") (pintype "passive"))
    )
    (net (code "84") (name "Net-(JP2-Pad3)") (class "Default")
      (node (ref "JP2") (pin "3") (pinfunction "3_3") (pintype "passive"))
      (node (ref "R4") (pin "1") (pinfunction "1_1") (pintype "passive"))
    )
    (net (code "85") (name "Net-(JP2-Pad4)") (class "Default")
      (node (ref "JP2") (pin "4") (pinfunction "4_4") (pintype "passive"))
      (node (ref "R3") (pin "1") (pinfunction "1_1") (pintype "passive"))
    )
    (net (code "86") (name "Net-(JP4-Pad1)") (class "Default")
      (node (ref "JP4") (pin "1") (pinfunction "1_1") (pintype "passive"))
      (node (ref "R42") (pin "2") (pinfunction "2_2") (pintype "passive"))
    )
    (net (code "87") (name "Net-(JP5-Pad2)") (class "Default")
      (node (ref "JP5") (pin "2") (pinfunction "2_2") (pintype "passive"))
      (node (ref "R12") (pin "2") (pinfunction "2_2") (pintype "passive"))
    )
    (net (code "88") (name "Net-(JP5-Pad4)") (class "Default")
      (node (ref "JP5") (pin "4") (pinfunction "4_4") (pintype "passive"))
      (node (ref "R14") (pin "2") (pinfunction "2_2") (pintype "passive"))
    )
    (net (code "89") (name "Net-(Q1-B)") (class "Default")
      (node (ref "Q1") (pin "1") (pinfunction "B_1") (pintype "passive"))
      (node (ref "R8") (pin "2") (pinfunction "2_2") (pintype "passive"))
    )
    (net (code "90") (name "Net-(Q2-D)") (class "Default")
      (node (ref "Q2") (pin "2") (pinfunction "D_2") (pintype "passive"))
      (node (ref "Q2") (pin "4") (pinfunction "D2_4") (pintype "passive"))
      (node (ref "X5") (pin "2") (pinfunction "2_2") (pintype "passive"))
    )
    (net (code "91") (name "Net-(Q2-G)") (class "Default")
      (node (ref "Q2") (pin "1") (pinfunction "G_1") (pintype "passive"))
      (node (ref "R9") (pin "2") (pinfunction "2_2") (pintype "passive"))
    )
    (net (code "92") (name "Net-(Q3-G)") (class "Default")
      (node (ref "Q3") (pin "1") (pinfunction "G_1") (pintype "passive"))
      (node (ref "R15") (pin "2") (pinfunction "2_2") (pintype "passive"))
    )
    (net (code "93") (name "Net-(Q4-G)") (class "Default")
      (node (ref "Q4") (pin "1") (pinfunction "G_1") (pintype "passive"))
      (node (ref "R17") (pin "2") (pinfunction "2_2") (pintype "passive"))
    )
    (net (code "94") (name "Net-(Q5-B)") (class "Default")
      (node (ref "D2") (pin "C") (pinfunction "C_C") (pintype "passive"))
      (node (ref "Q5") (pin "1") (pinfunction "B_1") (pintype "passive"))
      (node (ref "R19") (pin "1") (pinfunction "1_1") (pintype "passive"))
    )
    (net (code "95") (name "Net-(R6-Pad2)") (class "Default")
      (node (ref "R6") (pin "2") (pinfunction "2_2") (pintype "passive"))
      (node (ref "X5") (pin "1") (pinfunction "1_1") (pintype "passive"))
    )
    (net (code "96") (name "Net-(R52-Pad2)") (class "Default")
      (node (ref "R52") (pin "2") (pinfunction "2_2") (pintype "passive"))
      (node (ref "R52") (pin "3") (pinfunction "3_3") (pintype "passive"))
      (node (ref "R53") (pin "1") (pinfunction "1_1") (pintype "passive"))
    )
    (net (code "97") (name "Net-(R63-Pad2)") (class "Default")
      (node (ref "R63") (pin "2") (pinfunction "2_2") (pintype "passive"))
      (node (ref "R64") (pin "1") (pinfunction "1_1") (pintype "passive"))
    )
    (net (code "98") (name "Net-(R65-Pad2)") (class "Default")
      (node (ref "R65") (pin "2") (pinfunction "2_2") (pintype "passive"))
      (node (ref "R66") (pin "2") (pinfunction "2_2") (pintype "passive"))
    )
    (net (code "99") (name "Net-(R71-Pad2)") (class "Default")
      (node (ref "R71") (pin "2") (pinfunction "2_2") (pintype "passive"))
      (node (ref "R72") (pin "2") (pinfunction "2_2") (pintype "passive"))
    )
    (net (code "100") (name "Net-(R75-Pad2)") (class "Default")
      (node (ref "R75") (pin "2") (pinfunction "2_2") (pintype "passive"))
      (node (ref "R76") (pin "1") (pinfunction "1_1") (pintype "passive"))
    )
    (net (code "101") (name "Net-(S1-O)") (class "Default")
      (node (ref "C23") (pin "1") (pinfunction "1_1") (pintype "passive"))
      (node (ref "L4") (pin "1") (pinfunction "1_1") (pintype "passive"))
      (node (ref "S1") (pin "3") (pinfunction "O_3") (pintype "passive"))
    )
    (net (code "102") (name "Net-(S1-P)") (class "Default")
      (node (ref "PF1") (pin "2") (pinfunction "2_2") (pintype "passive"))
      (node (ref "S1") (pin "2") (pinfunction "P_2") (pintype "passive"))
    )
    (net (code "103") (name "Net-(U1-VBAT)") (class "Default")
      (node (ref "B1") (pin "+") (pinfunction "+_+") (pintype "passive"))
      (node (ref "U1") (pin "3") (pinfunction "VBAT_3") (pintype "power_in"))
    )
    (net (code "104") (name "Net-(U1-X1)") (class "Default")
      (node (ref "U1") (pin "1") (pinfunction "X1_1") (pintype "passive"))
      (node (ref "Y4") (pin "2") (pinfunction "2_2") (pintype "passive"))
    )
    (net (code "105") (name "Net-(U1-X2)") (class "Default")
      (node (ref "U1") (pin "2") (pinfunction "X2_2") (pintype "passive"))
      (node (ref "Y4") (pin "1") (pinfunction "1_1") (pintype "passive"))
    )
    (net (code "106") (name "Net-(U2-AREF)") (class "Default")
      (node (ref "C8") (pin "1") (pinfunction "1_1") (pintype "passive"))
      (node (ref "U2") (pin "62") (pinfunction "AREF_62") (pintype "bidirectional"))
    )
    (net (code "107") (name "Net-(U2-XTAL1)") (class "Default")
      (node (ref "C7") (pin "1") (pinfunction "1_1") (pintype "passive"))
      (node (ref "U2") (pin "24") (pinfunction "XTAL1_24") (pintype "bidirectional"))
      (node (ref "Y1") (pin "1") (pinfunction "1_1") (pintype "passive"))
    )
    (net (code "108") (name "Net-(U2-XTAL2)") (class "Default")
      (node (ref "C6") (pin "1") (pinfunction "1_1") (pintype "passive"))
      (node (ref "U2") (pin "23") (pinfunction "XTAL2_23") (pintype "bidirectional"))
      (node (ref "Y1") (pin "2") (pinfunction "2_2") (pintype "passive"))
    )
    (net (code "109") (name "Net-(U3A-C1+)") (class "Default")
      (node (ref "C10") (pin "1") (pinfunction "1_1") (pintype "passive"))
      (node (ref "U3") (pin "28") (pinfunction "C1+_28") (pintype "passive"))
    )
    (net (code "110") (name "Net-(U3A-C1-)") (class "Default")
      (node (ref "C10") (pin "2") (pinfunction "2_2") (pintype "passive"))
      (node (ref "U3") (pin "24") (pinfunction "C1-_24") (pintype "passive"))
    )
    (net (code "111") (name "Net-(U3A-C2+)") (class "Default")
      (node (ref "C13") (pin "1") (pinfunction "1_1") (pintype "passive"))
      (node (ref "U3") (pin "1") (pinfunction "C2+_1") (pintype "passive"))
    )
    (net (code "112") (name "Net-(U3A-C2-)") (class "Default")
      (node (ref "C13") (pin "2") (pinfunction "2_2") (pintype "passive"))
      (node (ref "U3") (pin "2") (pinfunction "C2-_2") (pintype "passive"))
    )
    (net (code "113") (name "Net-(U3A-V+)") (class "Default")
      (node (ref "C11") (pin "2") (pinfunction "2_2") (pintype "passive"))
      (node (ref "U3") (pin "27") (pinfunction "V+_27") (pintype "passive"))
    )
    (net (code "114") (name "Net-(U3A-V-)") (class "Default")
      (node (ref "C12") (pin "2") (pinfunction "2_2") (pintype "passive"))
      (node (ref "U3") (pin "3") (pinfunction "V-_3") (pintype "passive"))
    )
    (net (code "115") (name "Net-(U5A--IN)") (class "Default")
      (node (ref "C29") (pin "1") (pinfunction "1_1") (pintype "passive"))
      (node (ref "R25") (pin "1") (pinfunction "1_1") (pintype "passive"))
      (node (ref "R28") (pin "2") (pinfunction "2_2") (pintype "passive"))
      (node (ref "U5") (pin "2") (pinfunction "-IN_2") (pintype "input"))
    )
    (net (code "116") (name "Net-(U5A-OUT)") (class "Default")
      (node (ref "C29") (pin "2") (pinfunction "2_2") (pintype "passive"))
      (node (ref "C32") (pin "1") (pinfunction "1_1") (pintype "passive"))
      (node (ref "R25") (pin "2") (pinfunction "2_2") (pintype "passive"))
      (node (ref "U5") (pin "1") (pinfunction "OUT_1") (pintype "output"))
    )
    (net (code "117") (name "Net-(U5B-+IN)") (class "Default")
      (node (ref "C34") (pin "2") (pinfunction "2_2") (pintype "passive"))
      (node (ref "R24") (pin "2") (pinfunction "2_2") (pintype "passive"))
      (node (ref "U5") (pin "5") (pinfunction "+IN_5") (pintype "input"))
    )
    (net (code "118") (name "Net-(U5B--IN)") (class "Default")
      (node (ref "R30") (pin "2") (pinfunction "2_2") (pintype "passive"))
      (node (ref "R36") (pin "2") (pinfunction "2_2") (pintype "passive"))
      (node (ref "U5") (pin "6") (pinfunction "-IN_6") (pintype "input"))
      (node (ref "U5") (pin "7") (pinfunction "OUT_7") (pintype "output"))
    )
    (net (code "119") (name "Net-(U5C-+IN)") (class "Default")
      (node (ref "C35") (pin "2") (pinfunction "2_2") (pintype "passive"))
      (node (ref "C36") (pin "1") (pinfunction "1_1") (pintype "passive"))
      (node (ref "R38") (pin "1") (pinfunction "1_1") (pintype "passive"))
      (node (ref "U5") (pin "10") (pinfunction "+IN_10") (pintype "input"))
    )
    (net (code "120") (name "Net-(U5C--IN)") (class "Default")
      (node (ref "C36") (pin "2") (pinfunction "2_2") (pintype "passive"))
      (node (ref "R34") (pin "2") (pinfunction "2_2") (pintype "passive"))
      (node (ref "R39") (pin "1") (pinfunction "1_1") (pintype "passive"))
      (node (ref "U5") (pin "9") (pinfunction "-IN_9") (pintype "input"))
    )
    (net (code "121") (name "Net-(U5C-OUT)") (class "Default")
      (node (ref "R29") (pin "2") (pinfunction "2_2") (pintype "passive"))
      (node (ref "R34") (pin "1") (pinfunction "1_1") (pintype "passive"))
      (node (ref "U5") (pin "8") (pinfunction "OUT_8") (pintype "output"))
    )
    (net (code "122") (name "Net-(U5D-+IN)") (class "Default")
      (node (ref "C37") (pin "1") (pinfunction "1_1") (pintype "passive"))
      (node (ref "C38") (pin "2") (pinfunction "2_2") (pintype "passive"))
      (node (ref "R29") (pin "1") (pinfunction "1_1") (pintype "passive"))
      (node (ref "U5") (pin "12") (pinfunction "+IN_12") (pintype "input"))
    )
    (net (code "123") (name "Net-(U5D--IN)") (class "Default")
      (node (ref "C37") (pin "2") (pinfunction "2_2") (pintype "passive"))
      (node (ref "R35") (pin "2") (pinfunction "2_2") (pintype "passive"))
      (node (ref "R40") (pin "1") (pinfunction "1_1") (pintype "passive"))
      (node (ref "U5") (pin "13") (pinfunction "-IN_13") (pintype "input"))
    )
    (net (code "124") (name "Net-(U5D-OUT)") (class "Default")
      (node (ref "R31") (pin "2") (pinfunction "2_2") (pintype "passive"))
      (node (ref "R35") (pin "1") (pinfunction "1_1") (pintype "passive"))
      (node (ref "U5") (pin "14") (pinfunction "OUT_14") (pintype "output"))
    )
    (net (code "125") (name "Net-(U6A-EST)") (class "Default")
      (node (ref "R32") (pin "1") (pinfunction "1_1") (pintype "passive"))
      (node (ref "U6") (pin "16") (pinfunction "EST_16") (pintype "input"))
    )
    (net (code "126") (name "Net-(U6A-GS)") (class "Default")
      (node (ref "C40") (pin "1") (pinfunction "1_1") (pintype "passive"))
      (node (ref "R41") (pin "1") (pinfunction "1_1") (pintype "passive"))
      (node (ref "U6") (pin "3") (pinfunction "GS_3") (pintype "input"))
    )
    (net (code "127") (name "Net-(U6A-IN+)") (class "Default")
      (node (ref "U6") (pin "1") (pinfunction "IN+_1") (pintype "input"))
      (node (ref "U6") (pin "4") (pinfunction "VREF_4") (pintype "output"))
    )
    (net (code "128") (name "Net-(U6A-IN-)") (class "Default")
      (node (ref "C40") (pin "2") (pinfunction "2_2") (pintype "passive"))
      (node (ref "R41") (pin "2") (pinfunction "2_2") (pintype "passive"))
      (node (ref "R45") (pin "2") (pinfunction "2_2") (pintype "passive"))
      (node (ref "U6") (pin "2") (pinfunction "IN-_2") (pintype "input"))
    )
    (net (code "129") (name "Net-(U6A-OSC1)") (class "Default")
      (node (ref "U6") (pin "7") (pinfunction "OSC1_7") (pintype "input"))
      (node (ref "Y2") (pin "2") (pinfunction "2_2") (pintype "passive"))
    )
    (net (code "130") (name "Net-(U6A-OSC2)") (class "Default")
      (node (ref "U6") (pin "8") (pinfunction "OSC2_8") (pintype "bidirectional"))
      (node (ref "Y2") (pin "1") (pinfunction "1_1") (pintype "passive"))
    )
    (net (code "131") (name "Net-(U6A-ST{slash}GT)") (class "Default")
      (node (ref "C30") (pin "1") (pinfunction "1_1") (pintype "passive"))
      (node (ref "R32") (pin "2") (pinfunction "2_2") (pintype "passive"))
      (node (ref "U6") (pin "17") (pinfunction "ST/GT_17") (pintype "bidirectional"))
    )
    (net (code "132") (name "Net-(U7A-COM)") (class "Default")
      (node (ref "C44") (pin "1") (pinfunction "1_1") (pintype "passive"))
      (node (ref "R46") (pin "1") (pinfunction "1_1") (pintype "passive"))
      (node (ref "U7") (pin "2") (pinfunction "COM_2") (pintype "passive"))
    )
    (net (code "133") (name "Net-(U7B-COM)") (class "Default")
      (node (ref "C58") (pin "1") (pinfunction "1_1") (pintype "passive"))
      (node (ref "R62") (pin "1") (pinfunction "1_1") (pintype "passive"))
      (node (ref "U7") (pin "6") (pinfunction "COM_6") (pintype "passive"))
    )
    (net (code "134") (name "Net-(U8A-A{slash}D_CAP1)") (class "Default")
      (node (ref "C55") (pin "+") (pinfunction "+_+") (pintype "passive"))
      (node (ref "U8") (pin "10") (pinfunction "A/D_CAP1_10") (pintype "output"))
    )
    (net (code "135") (name "Net-(U8A-A{slash}D_CAP2)") (class "Default")
      (node (ref "C56") (pin "+") (pinfunction "+_+") (pintype "passive"))
      (node (ref "U8") (pin "11") (pinfunction "A/D_CAP2_11") (pintype "output"))
    )
    (net (code "136") (name "Net-(U8A-RX_AMP_IN)") (class "Default")
      (node (ref "C46") (pin "2") (pinfunction "2_2") (pintype "passive"))
      (node (ref "JP4") (pin "2") (pinfunction "2_2") (pintype "passive"))
      (node (ref "R43") (pin "1") (pinfunction "1_1") (pintype "passive"))
      (node (ref "R47") (pin "2") (pinfunction "2_2") (pintype "passive"))
      (node (ref "U8") (pin "14") (pinfunction "RX_AMP_IN_14") (pintype "input"))
    )
    (net (code "137") (name "Net-(U8A-RX_AMP_OUT)") (class "Default")
      (node (ref "C41") (pin "1") (pinfunction "1_1") (pintype "passive"))
      (node (ref "C46") (pin "1") (pinfunction "1_1") (pintype "passive"))
      (node (ref "R42") (pin "1") (pinfunction "1_1") (pintype "passive"))
      (node (ref "R47") (pin "1") (pinfunction "1_1") (pintype "passive"))
      (node (ref "U8") (pin "15") (pinfunction "RX_AMP_OUT_15") (pintype "output"))
    )
    (net (code "138") (name "Net-(U8A-SUM_IN)") (class "Default")
      (node (ref "C49") (pin "1") (pinfunction "1_1") (pintype "passive"))
      (node (ref "R54") (pin "1") (pinfunction "1_1") (pintype "passive"))
      (node (ref "R57") (pin "2") (pinfunction "2_2") (pintype "passive"))
      (node (ref "R58") (pin "2") (pinfunction "2_2") (pintype "passive"))
      (node (ref "U8") (pin "18") (pinfunction "SUM_IN_18") (pintype "input"))
    )
    (net (code "139") (name "Net-(U8A-SUM_OUT)") (class "Default")
      (node (ref "C49") (pin "2") (pinfunction "2_2") (pintype "passive"))
      (node (ref "R54") (pin "2") (pinfunction "2_2") (pintype "passive"))
      (node (ref "U8") (pin "19") (pinfunction "SUM_OUT_19") (pintype "output"))
    )
    (net (code "140") (name "Net-(U8A-TX_AUD_OUT)") (class "Default")
      (node (ref "R57") (pin "1") (pinfunction "1_1") (pintype "passive"))
      (node (ref "U8") (pin "17") (pinfunction "TX_AUD_OUT_17") (pintype "output"))
    )
    (net (code "141") (name "Net-(U8A-TX_SUB_AUD_OUT)") (class "Default")
      (node (ref "R58") (pin "1") (pinfunction "1_1") (pintype "passive"))
      (node (ref "U8") (pin "21") (pinfunction "TX_SUB_AUD_OUT_21") (pintype "output"))
    )
    (net (code "142") (name "Net-(U8A-VBIAS)") (class "Default")
      (node (ref "C57") (pin "1") (pinfunction "1_1") (pintype "passive"))
      (node (ref "U8") (pin "13") (pinfunction "VBIAS_13") (pintype "input"))
    )
    (net (code "143") (name "Net-(U8A-XTAL)") (class "Default")
      (node (ref "C54") (pin "1") (pinfunction "1_1") (pintype "passive"))
      (node (ref "R55") (pin "1") (pinfunction "1_1") (pintype "passive"))
      (node (ref "U8") (pin "1") (pinfunction "XTAL_1") (pintype "output"))
      (node (ref "Y3") (pin "2") (pinfunction "2_2") (pintype "passive"))
    )
    (net (code "144") (name "Net-(U8A-XTAL{slash}CLOCK)") (class "Default")
      (node (ref "C53") (pin "1") (pinfunction "1_1") (pintype "passive"))
      (node (ref "R55") (pin "2") (pinfunction "2_2") (pintype "passive"))
      (node (ref "U8") (pin "2") (pinfunction "XTAL/CLOCK_2") (pintype "input"))
      (node (ref "Y3") (pin "1") (pinfunction "1_1") (pintype "passive"))
    )
    (net (code "145") (name "Net-(U9-AM_CAP)") (class "Default")
      (node (ref "C67") (pin "+") (pinfunction "+_+") (pintype "passive"))
      (node (ref "U9") (pin "14") (pinfunction "AM_CAP_14") (pintype "output"))
    )
    (net (code "146") (name "Net-(U9-ANA_IN+)") (class "Default")
      (node (ref "C59") (pin "2") (pinfunction "2_2") (pintype "passive"))
      (node (ref "U9") (pin "17") (pinfunction "ANA_IN+_17") (pintype "input"))
    )
    (net (code "147") (name "Net-(U9-ANA_IN-)") (class "Default")
      (node (ref "C63") (pin "2") (pinfunction "2_2") (pintype "passive"))
      (node (ref "U9") (pin "16") (pinfunction "ANA_IN-_16") (pintype "input"))
    )
    (net (code "148") (name "Net-(U9-AUD_OUT)") (class "Default")
      (node (ref "C64") (pin "1") (pinfunction "1_1") (pintype "passive"))
      (node (ref "U9") (pin "13") (pinfunction "AUD_OUT_13") (pintype "output"))
    )
    (net (code "149") (name "Net-(U10A-+IN)") (class "Default")
      (node (ref "C66") (pin "1") (pinfunction "1_1") (pintype "passive"))
      (node (ref "R74") (pin "1") (pinfunction "1_1") (pintype "passive"))
      (node (ref "R78") (pin "2") (pinfunction "2_2") (pintype "passive"))
      (node (ref "U10") (pin "3") (pinfunction "+IN_3") (pintype "input"))
    )
    (net (code "150") (name "Net-(U10B--IN)") (class "Default")
      (node (ref "C48") (pin "1") (pinfunction "1_1") (pintype "passive"))
      (node (ref "R52") (pin "1") (pinfunction "1_1") (pintype "passive"))
      (node (ref "R60") (pin "2") (pinfunction "2_2") (pintype "passive"))
      (node (ref "U10") (pin "6") (pinfunction "-IN_6") (pintype "input"))
    )
    (net (code "151") (name "Net-(U10B-OUT)") (class "Default")
      (node (ref "R53") (pin "2") (pinfunction "2_2") (pintype "passive"))
      (node (ref "R56") (pin "2") (pinfunction "2_2") (pintype "passive"))
      (node (ref "R83") (pin "1") (pinfunction "1_1") (pintype "passive"))
      (node (ref "U10") (pin "7") (pinfunction "OUT_7") (pintype "output"))
    )
    (net (code "152") (name "Net-(U10C--IN)") (class "Default")
      (node (ref "C42") (pin "1") (pinfunction "1_1") (pintype "passive"))
      (node (ref "R44") (pin "1") (pinfunction "1_1") (pintype "passive"))
      (node (ref "R48") (pin "2") (pinfunction "2_2") (pintype "passive"))
      (node (ref "U10") (pin "9") (pinfunction "-IN_9") (pintype "input"))
    )
    (net (code "153") (name "Net-(U10C-OUT)") (class "Default")
      (node (ref "C42") (pin "2") (pinfunction "2_2") (pintype "passive"))
      (node (ref "R44") (pin "2") (pinfunction "2_2") (pintype "passive"))
      (node (ref "R82") (pin "1") (pinfunction "1_1") (pintype "passive"))
      (node (ref "U10") (pin "8") (pinfunction "OUT_8") (pintype "output"))
    )
    (net (code "154") (name "Net-(U10D-+IN)") (class "Default")
      (node (ref "C65") (pin "1") (pinfunction "1_1") (pintype "passive"))
      (node (ref "R73") (pin "1") (pinfunction "1_1") (pintype "passive"))
      (node (ref "R77") (pin "2") (pinfunction "2_2") (pintype "passive"))
      (node (ref "U10") (pin "12") (pinfunction "+IN_12") (pintype "input"))
    )
    (net (code "155") (name "Net-(U12-IN)") (class "Default")
      (node (ref "C3") (pin "+") (pinfunction "+_+") (pintype "passive"))
      (node (ref "C79") (pin "+") (pinfunction "+_+") (pintype "passive"))
      (node (ref "L2") (pin "1") (pinfunction "1_1") (pintype "passive"))
      (node (ref "L3") (pin "1") (pinfunction "1_1") (pintype "passive"))
      (node (ref "U12") (pin "3") (pinfunction "IN_3") (pintype "input"))
    )
    (net (code "156") (name "Net-(X1A-SK)") (class "Default")
      (node (ref "L1") (pin "1") (pinfunction "1_1") (pintype "passive"))
      (node (ref "X1") (pin "1") (pinfunction "SK_1") (pintype "passive"))
    )
    (net (code "157") (name "Net-(X1B-SK)") (class "Default")
      (node (ref "L1") (pin "2") (pinfunction "2_2") (pintype "passive"))
      (node (ref "X1") (pin "2") (pinfunction "SK_2") (pintype "passive"))
    )
    (net (code "158") (name "PA0") (class "Default")
      (node (ref "J1") (pin "7") (pinfunction "DB0_7") (pintype "passive"))
      (node (ref "U2") (pin "51") (pinfunction "(AD0)PA0_51") (pintype "bidirectional"))
    )
    (net (code "159") (name "PA1") (class "Default")
      (node (ref "J1") (pin "8") (pinfunction "DB1_8") (pintype "passive"))
      (node (ref "U2") (pin "50") (pinfunction "(AD1)PA1_50") (pintype "bidirectional"))
    )
    (net (code "160") (name "PA2") (class "Default")
      (node (ref "J1") (pin "9") (pinfunction "DB2_9") (pintype "passive"))
      (node (ref "U2") (pin "49") (pinfunction "(AD2)PA2_49") (pintype "bidirectional"))
    )
    (net (code "161") (name "PA3") (class "Default")
      (node (ref "J1") (pin "10") (pinfunction "DB3_10") (pintype "passive"))
      (node (ref "U2") (pin "48") (pinfunction "(AD3)PA3_48") (pintype "bidirectional"))
    )
    (net (code "162") (name "PA4") (class "Default")
      (node (ref "J1") (pin "11") (pinfunction "DB4_11") (pintype "passive"))
      (node (ref "U2") (pin "47") (pinfunction "(AD4)PA4_47") (pintype "bidirectional"))
    )
    (net (code "163") (name "PA5") (class "Default")
      (node (ref "J1") (pin "12") (pinfunction "DB5_12") (pintype "passive"))
      (node (ref "U2") (pin "46") (pinfunction "(AD5)PA5_46") (pintype "bidirectional"))
    )
    (net (code "164") (name "PA6") (class "Default")
      (node (ref "J1") (pin "13") (pinfunction "DB6_13") (pintype "passive"))
      (node (ref "U2") (pin "45") (pinfunction "(AD6)PA6_45") (pintype "bidirectional"))
    )
    (net (code "165") (name "PA7") (class "Default")
      (node (ref "J1") (pin "14") (pinfunction "DB7_14") (pintype "passive"))
      (node (ref "U2") (pin "44") (pinfunction "(AD7)PA7_44") (pintype "bidirectional"))
    )
    (net (code "166") (name "PTT") (class "Default")
      (node (ref "Q3") (pin "2") (pinfunction "D_2") (pintype "passive"))
      (node (ref "X3") (pin "1") (pinfunction "1_1") (pintype "passive"))
      (node (ref "X4") (pin "1") (pinfunction "1_1") (pintype "passive"))
    )
    (net (code "167") (name "PTT_DRIVE") (class "Default")
      (node (ref "R15") (pin "1") (pinfunction "1_1") (pintype "passive"))
      (node (ref "U2") (pin "36") (pinfunction "(A9)PC1_36") (pintype "output"))
    )
    (net (code "168") (name "RESET") (class "Default")
      (node (ref "C5") (pin "1") (pinfunction "1_1") (pintype "passive"))
      (node (ref "D1") (pin "A") (pinfunction "A_A") (pintype "passive"))
      (node (ref "JP1") (pin "6") (pinfunction "6_6") (pintype "passive"))
      (node (ref "JP2") (pin "5") (pinfunction "5_5") (pintype "passive"))
      (node (ref "R5") (pin "1") (pinfunction "1_1") (pintype "passive"))
      (node (ref "U2") (pin "20") (pinfunction "~{RESET}_20") (pintype "input"))
    )
    (net (code "169") (name "RX_AUDIO_OUT") (class "Default")
      (node (ref "C43") (pin "1") (pinfunction "1_1") (pintype "passive"))
      (node (ref "J2") (pin "1") (pinfunction "1_1") (pintype "passive"))
      (node (ref "TP6") (pin "TP") (pinfunction "TP_TP") (pintype "input"))
      (node (ref "U8") (pin "16") (pinfunction "RX_AUD_OUT_16") (pintype "output"))
      (node (ref "U8") (pin "20") (pinfunction "MOD1_IN_20") (pintype "input"))
    )
    (net (code "170") (name "RX_AUDIO_RET") (class "Default")
      (node (ref "J2") (pin "2") (pinfunction "2_2") (pintype "passive"))
      (node (ref "U7") (pin "5") (pinfunction "NO_5") (pintype "passive"))
    )
    (net (code "171") (name "SPI_MISO") (class "Default")
      (node (ref "J2") (pin "14") (pinfunction "14_14") (pintype "passive"))
      (node (ref "U2") (pin "13") (pinfunction "(MISO/PCINT3)PB3_13") (pintype "bidirectional"))
      (node (ref "U8") (pin "5") (pinfunction "REPLY_DATA_5") (pintype "bidirectional"))
      (node (ref "U9") (pin "3") (pinfunction "MISO_3") (pintype "bidirectional"))
    )
    (net (code "172") (name "SPI_MOSI") (class "Default")
      (node (ref "J2") (pin "12") (pinfunction "12_12") (pintype "passive"))
      (node (ref "U2") (pin "12") (pinfunction "(MOSI/PCINT2)PB2_12") (pintype "bidirectional"))
      (node (ref "U8") (pin "4") (pinfunction "COMMAND_DATA_4") (pintype "input"))
      (node (ref "U9") (pin "2") (pinfunction "MOSI_2") (pintype "bidirectional"))
    )
    (net (code "173") (name "SPI_SCK") (class "Default")
      (node (ref "J2") (pin "10") (pinfunction "10_10") (pintype "passive"))
      (node (ref "R4") (pin "2") (pinfunction "2_2") (pintype "passive"))
      (node (ref "U2") (pin "11") (pinfunction "(SCK/PCINT1)PB1_11") (pintype "bidirectional"))
      (node (ref "U8") (pin "3") (pinfunction "SERIAL_CLOCK_3") (pintype "input"))
      (node (ref "U9") (pin "28") (pinfunction "SCLK_28") (pintype "bidirectional"))
    )
    (net (code "174") (name "SPI_SS") (class "Default")
      (node (ref "J2") (pin "16") (pinfunction "16_16") (pintype "passive"))
      (node (ref "U2") (pin "33") (pinfunction "PG0(WR#)_33") (pintype "bidirectional"))
    )
    (net (code "175") (name "SS_ISD") (class "Default")
      (node (ref "U2") (pin "16") (pinfunction "(OC1B/PCINT6)PB6_16") (pintype "bidirectional"))
      (node (ref "U9") (pin "1") (pinfunction "~{SS}_1") (pintype "input"))
    )
    (net (code "176") (name "SS_MX828") (class "Default")
      (node (ref "U2") (pin "10") (pinfunction "~{(SS}/PCINT0)PB0_10") (pintype "bidirectional"))
      (node (ref "U8") (pin "6") (pinfunction "~{CS}_6") (pintype "input"))
    )
    (net (code "177") (name "TCK") (class "Default")
      (node (ref "JP1") (pin "1") (pinfunction "1_1") (pintype "passive"))
      (node (ref "RN1") (pin "1") (pinfunction "1_1") (pintype "passive"))
      (node (ref "U2") (pin "57") (pinfunction "PF4(ADC4/TCK)_57") (pintype "input"))
    )
    (net (code "178") (name "TDI") (class "Default")
      (node (ref "JP1") (pin "9") (pinfunction "9_9") (pintype "passive"))
      (node (ref "R12") (pin "1") (pinfunction "1_1") (pintype "passive"))
      (node (ref "RN1") (pin "4") (pinfunction "4_4") (pintype "passive"))
      (node (ref "U2") (pin "54") (pinfunction "PF7(ADC7/TDI)_54") (pintype "input"))
    )
    (net (code "179") (name "TDO") (class "Default")
      (node (ref "JP1") (pin "3") (pinfunction "3_3") (pintype "passive"))
      (node (ref "R14") (pin "1") (pinfunction "1_1") (pintype "passive"))
      (node (ref "RN1") (pin "3") (pinfunction "3_3") (pintype "passive"))
      (node (ref "U2") (pin "55") (pinfunction "PF6(ADC6/TDO)_55") (pintype "input"))
    )
    (net (code "180") (name "TMS") (class "Default")
      (node (ref "JP1") (pin "5") (pinfunction "5_5") (pintype "passive"))
      (node (ref "RN1") (pin "2") (pinfunction "2_2") (pintype "passive"))
      (node (ref "U2") (pin "56") (pinfunction "PF5(ADC5/TMS)_56") (pintype "input"))
    )
    (net (code "181") (name "TX_AUDIO") (class "Default")
      (node (ref "C52") (pin "2") (pinfunction "2_2") (pintype "passive"))
      (node (ref "J2") (pin "5") (pinfunction "5_5") (pintype "passive"))
      (node (ref "R61") (pin "2") (pinfunction "2_2") (pintype "passive"))
      (node (ref "X3") (pin "7") (pinfunction "7_7") (pintype "passive"))
      (node (ref "X4") (pin "7") (pinfunction "7_7") (pintype "passive"))
    )
    (net (code "182") (name "TX_TONE_OUT") (class "Default")
      (node (ref "C50") (pin "1") (pinfunction "1_1") (pintype "passive"))
      (node (ref "TP5") (pin "TP") (pinfunction "TP_TP") (pintype "input"))
      (node (ref "U8") (pin "23") (pinfunction "MOD2_23") (pintype "output"))
    )
    (net (code "183") (name "VBATT") (class "Default")
      (node (ref "C20") (pin "1") (pinfunction "1_1") (pintype "passive"))
      (node (ref "D7") (pin "C") (pinfunction "C_C") (pintype "passive"))
      (node (ref "R21") (pin "1") (pinfunction "1_1") (pintype "passive"))
      (node (ref "R23") (pin "2") (pinfunction "2_2") (pintype "passive"))
      (node (ref "U2") (pin "59") (pinfunction "PF2(ADC2)_59") (pintype "input"))
    )
    (net (code "184") (name "VREF") (class "Default")
      (node (ref "R24") (pin "1") (pinfunction "1_1") (pintype "passive"))
      (node (ref "U10") (pin "10") (pinfunction "+IN_10") (pintype "input"))
      (node (ref "U10") (pin "13") (pinfunction "-IN_13") (pintype "input"))
      (node (ref "U10") (pin "14") (pinfunction "OUT_14") (pintype "output"))
      (node (ref "U10") (pin "5") (pinfunction "+IN_5") (pintype "input"))
      (node (ref "U5") (pin "3") (pinfunction "+IN_3") (pintype "input"))
    )
    (net (code "185") (name "VSQL") (class "Default")
      (node (ref "C78") (pin "+") (pinfunction "+_+") (pintype "passive"))
      (node (ref "D10") (pin "C") (pinfunction "C_C") (pintype "passive"))
      (node (ref "R31") (pin "1") (pinfunction "1_1") (pintype "passive"))
      (node (ref "R37") (pin "1") (pinfunction "1_1") (pintype "passive"))
      (node (ref "TP3") (pin "TP") (pinfunction "TP_TP") (pintype "input"))
      (node (ref "U2") (pin "61") (pinfunction "PF0(ADC0)_61") (pintype "input"))
      (node (ref "U8") (pin "9") (pinfunction "COMP_IN_9") (pintype "input"))
    )
    (net (code "186") (name "VTEMP") (class "Default")
      (node (ref "C19") (pin "1") (pinfunction "1_1") (pintype "passive"))
      (node (ref "R20") (pin "1") (pinfunction "1_1") (pintype "passive"))
      (node (ref "R22") (pin "2") (pinfunction "2_2") (pintype "passive"))
      (node (ref "U2") (pin "60") (pinfunction "PF1(ADC1)_60") (pintype "input"))
    )
    (net (code "187") (name "XADC") (class "Default")
      (node (ref "J2") (pin "20") (pinfunction "20_20") (pintype "passive"))
      (node (ref "U2") (pin "58") (pinfunction "PF3(ADC3)_58") (pintype "input"))
    )
    (net (code "188") (name "unconnected-(J1-A-Pad15)") (class "Default")
      (node (ref "J1") (pin "15") (pinfunction "A_15") (pintype "passive"))
    )
    (net (code "189") (name "unconnected-(J1-C-Pad16)") (class "Default")
      (node (ref "J1") (pin "16") (pinfunction "C_16") (pintype "passive"))
    )
    (net (code "190") (name "unconnected-(JP1-Pad8)") (class "Default")
      (node (ref "JP1") (pin "8") (pinfunction "8_8") (pintype "passive"))
    )
    (net (code "191") (name "unconnected-(S1-S-Pad1)") (class "Default")
      (node (ref "S1") (pin "1") (pinfunction "S_1") (pintype "passive"))
    )
    (net (code "192") (name "unconnected-(U1-SQW{slash}OUT-Pad7)") (class "Default")
      (node (ref "U1") (pin "7") (pinfunction "SQW/OUT_7") (pintype "output"))
    )
    (net (code "193") (name "unconnected-(U3A-R1OUT-Pad19)") (class "Default")
      (node (ref "U3") (pin "19") (pinfunction "R1OUT_19") (pintype "output"))
    )
    (net (code "194") (name "unconnected-(U3A-R2OUTB-Pad20)") (class "Default")
      (node (ref "U3") (pin "20") (pinfunction "R2OUTB_20") (pintype "output"))
    )
    (net (code "195") (name "unconnected-(U3A-~{INVALID}-Pad21)") (class "Default")
      (node (ref "U3") (pin "21") (pinfunction "~{INVALID}_21") (pintype "output"))
    )
    (net (code "196") (name "unconnected-(U8A-COMP_OUT-Pad8)") (class "Default")
      (node (ref "U8") (pin "8") (pinfunction "COMP_OUT_8") (pintype "output"))
    )
  )
)
